# Power_iCESDuck-ShieldControler.net
KiCad netlist of a schematic drawn in EasyEDA
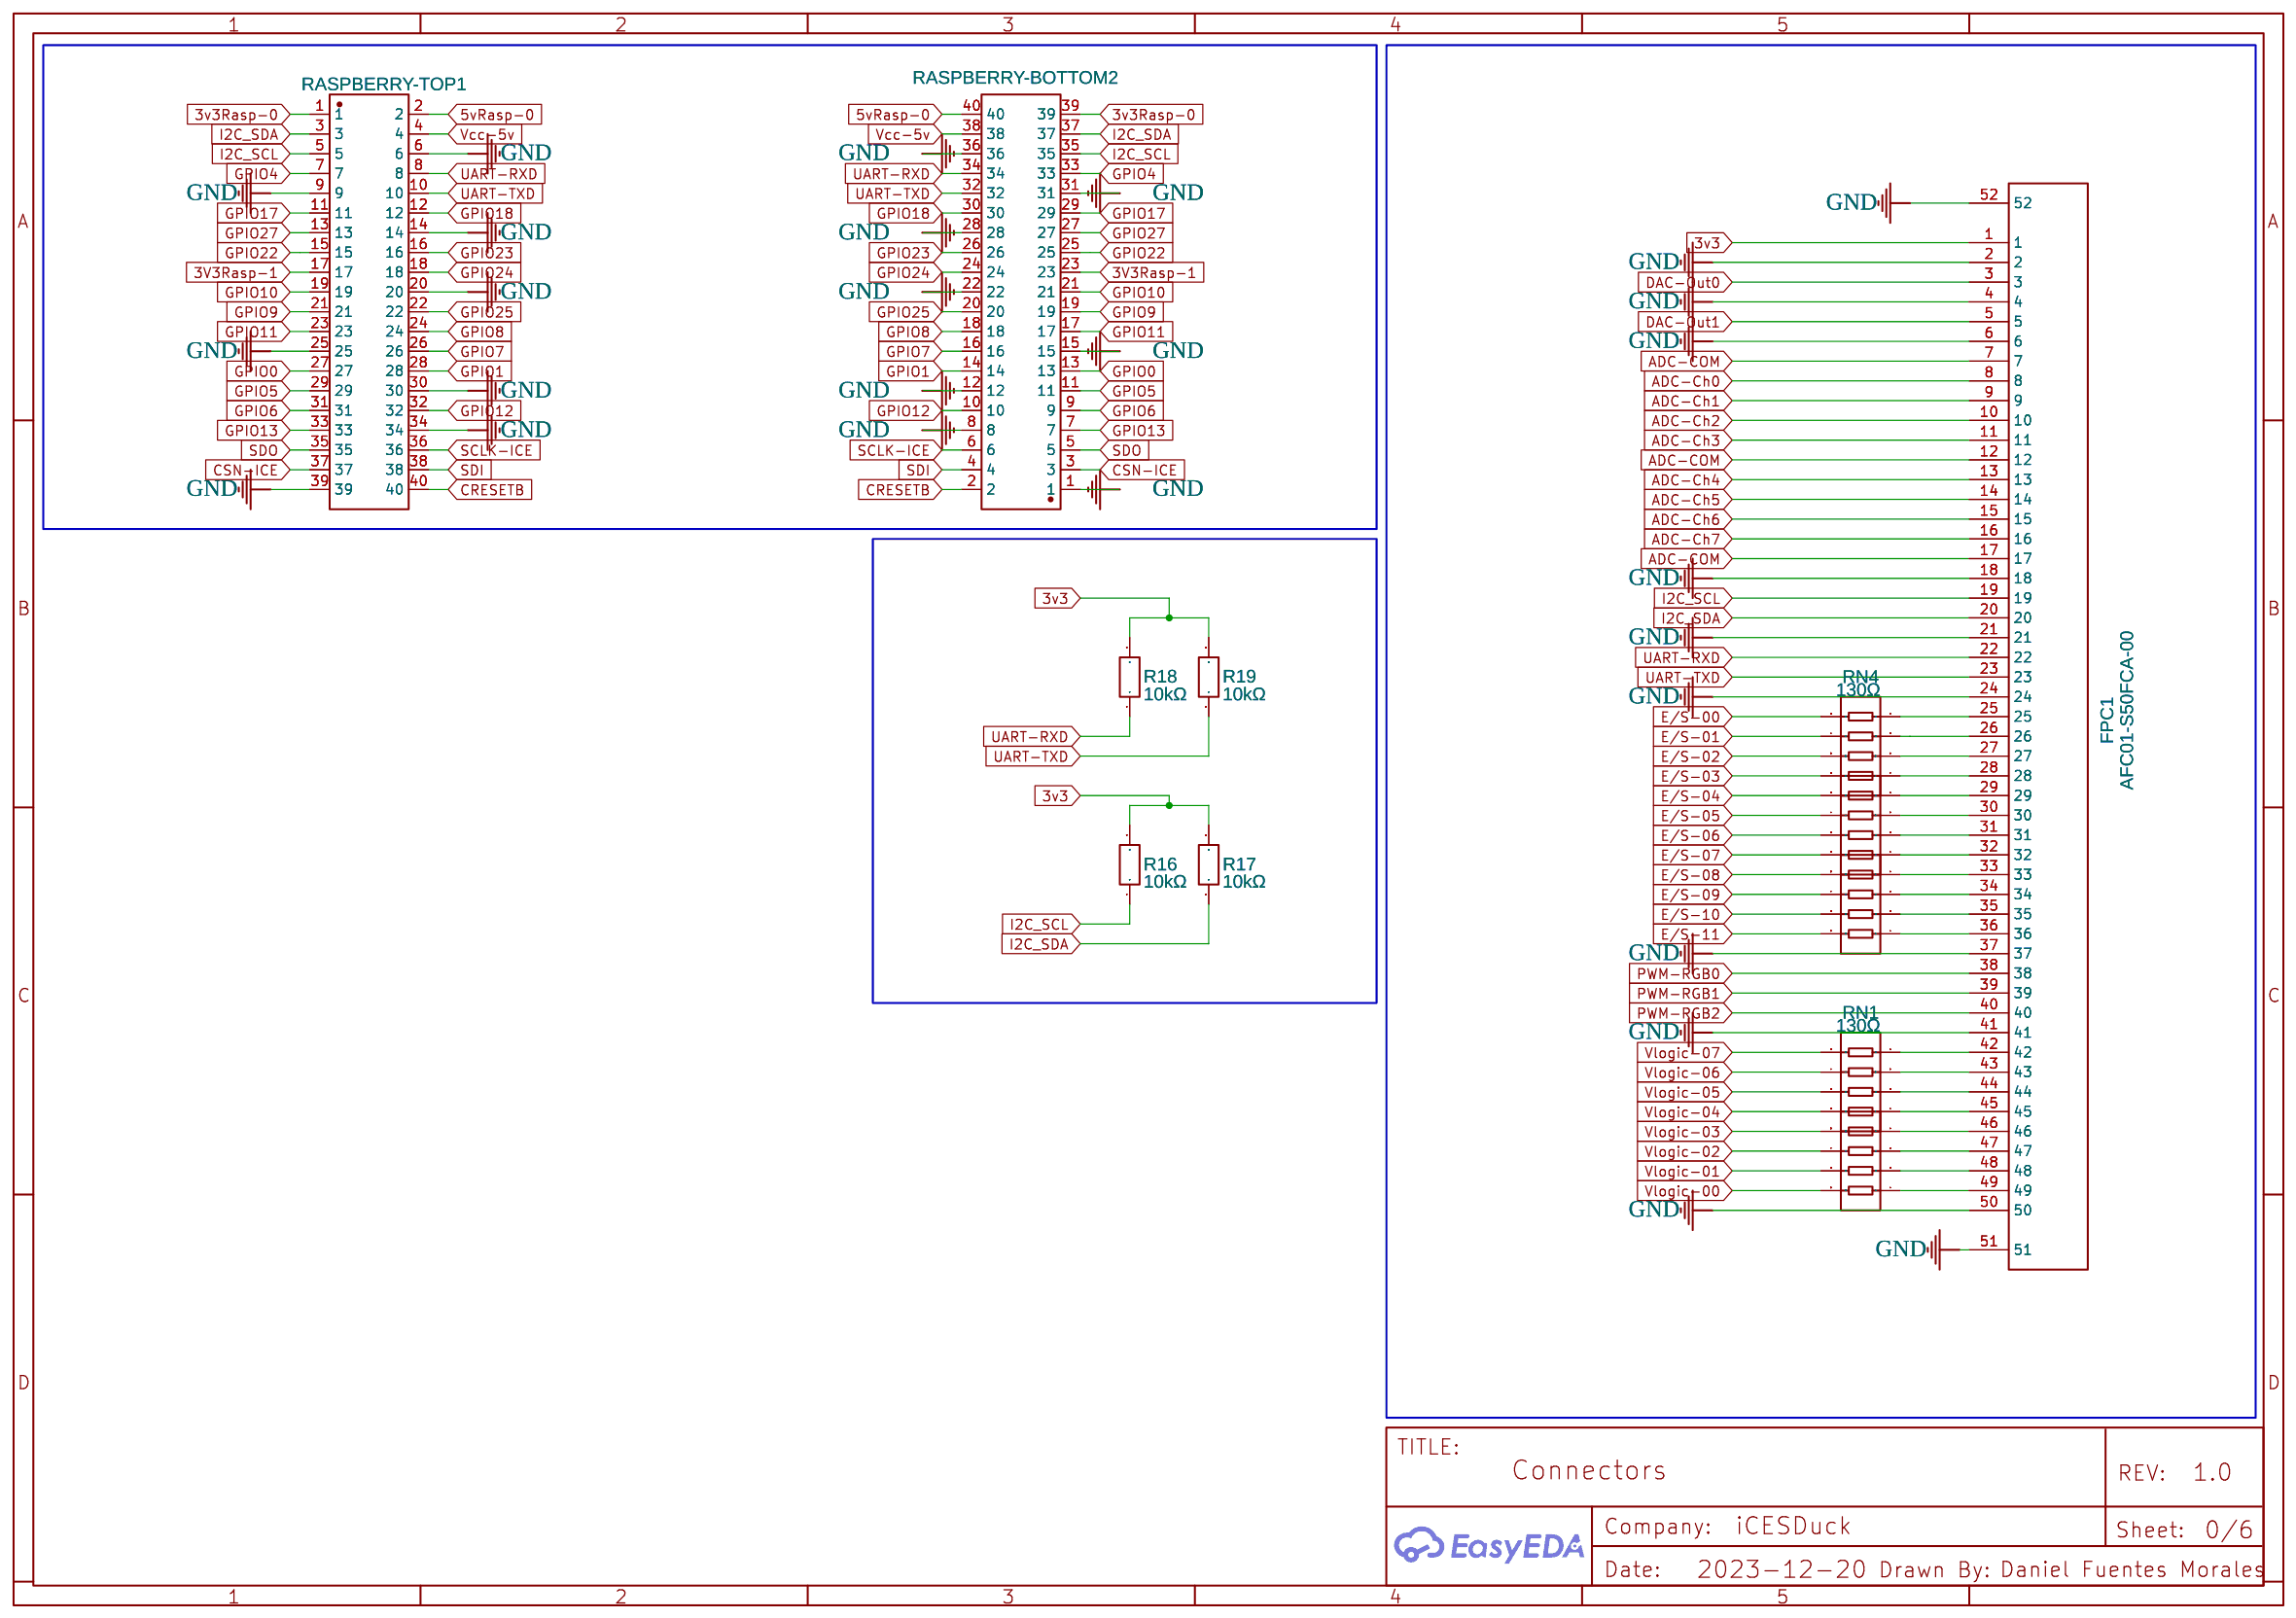
[diagram p0: Connectors]
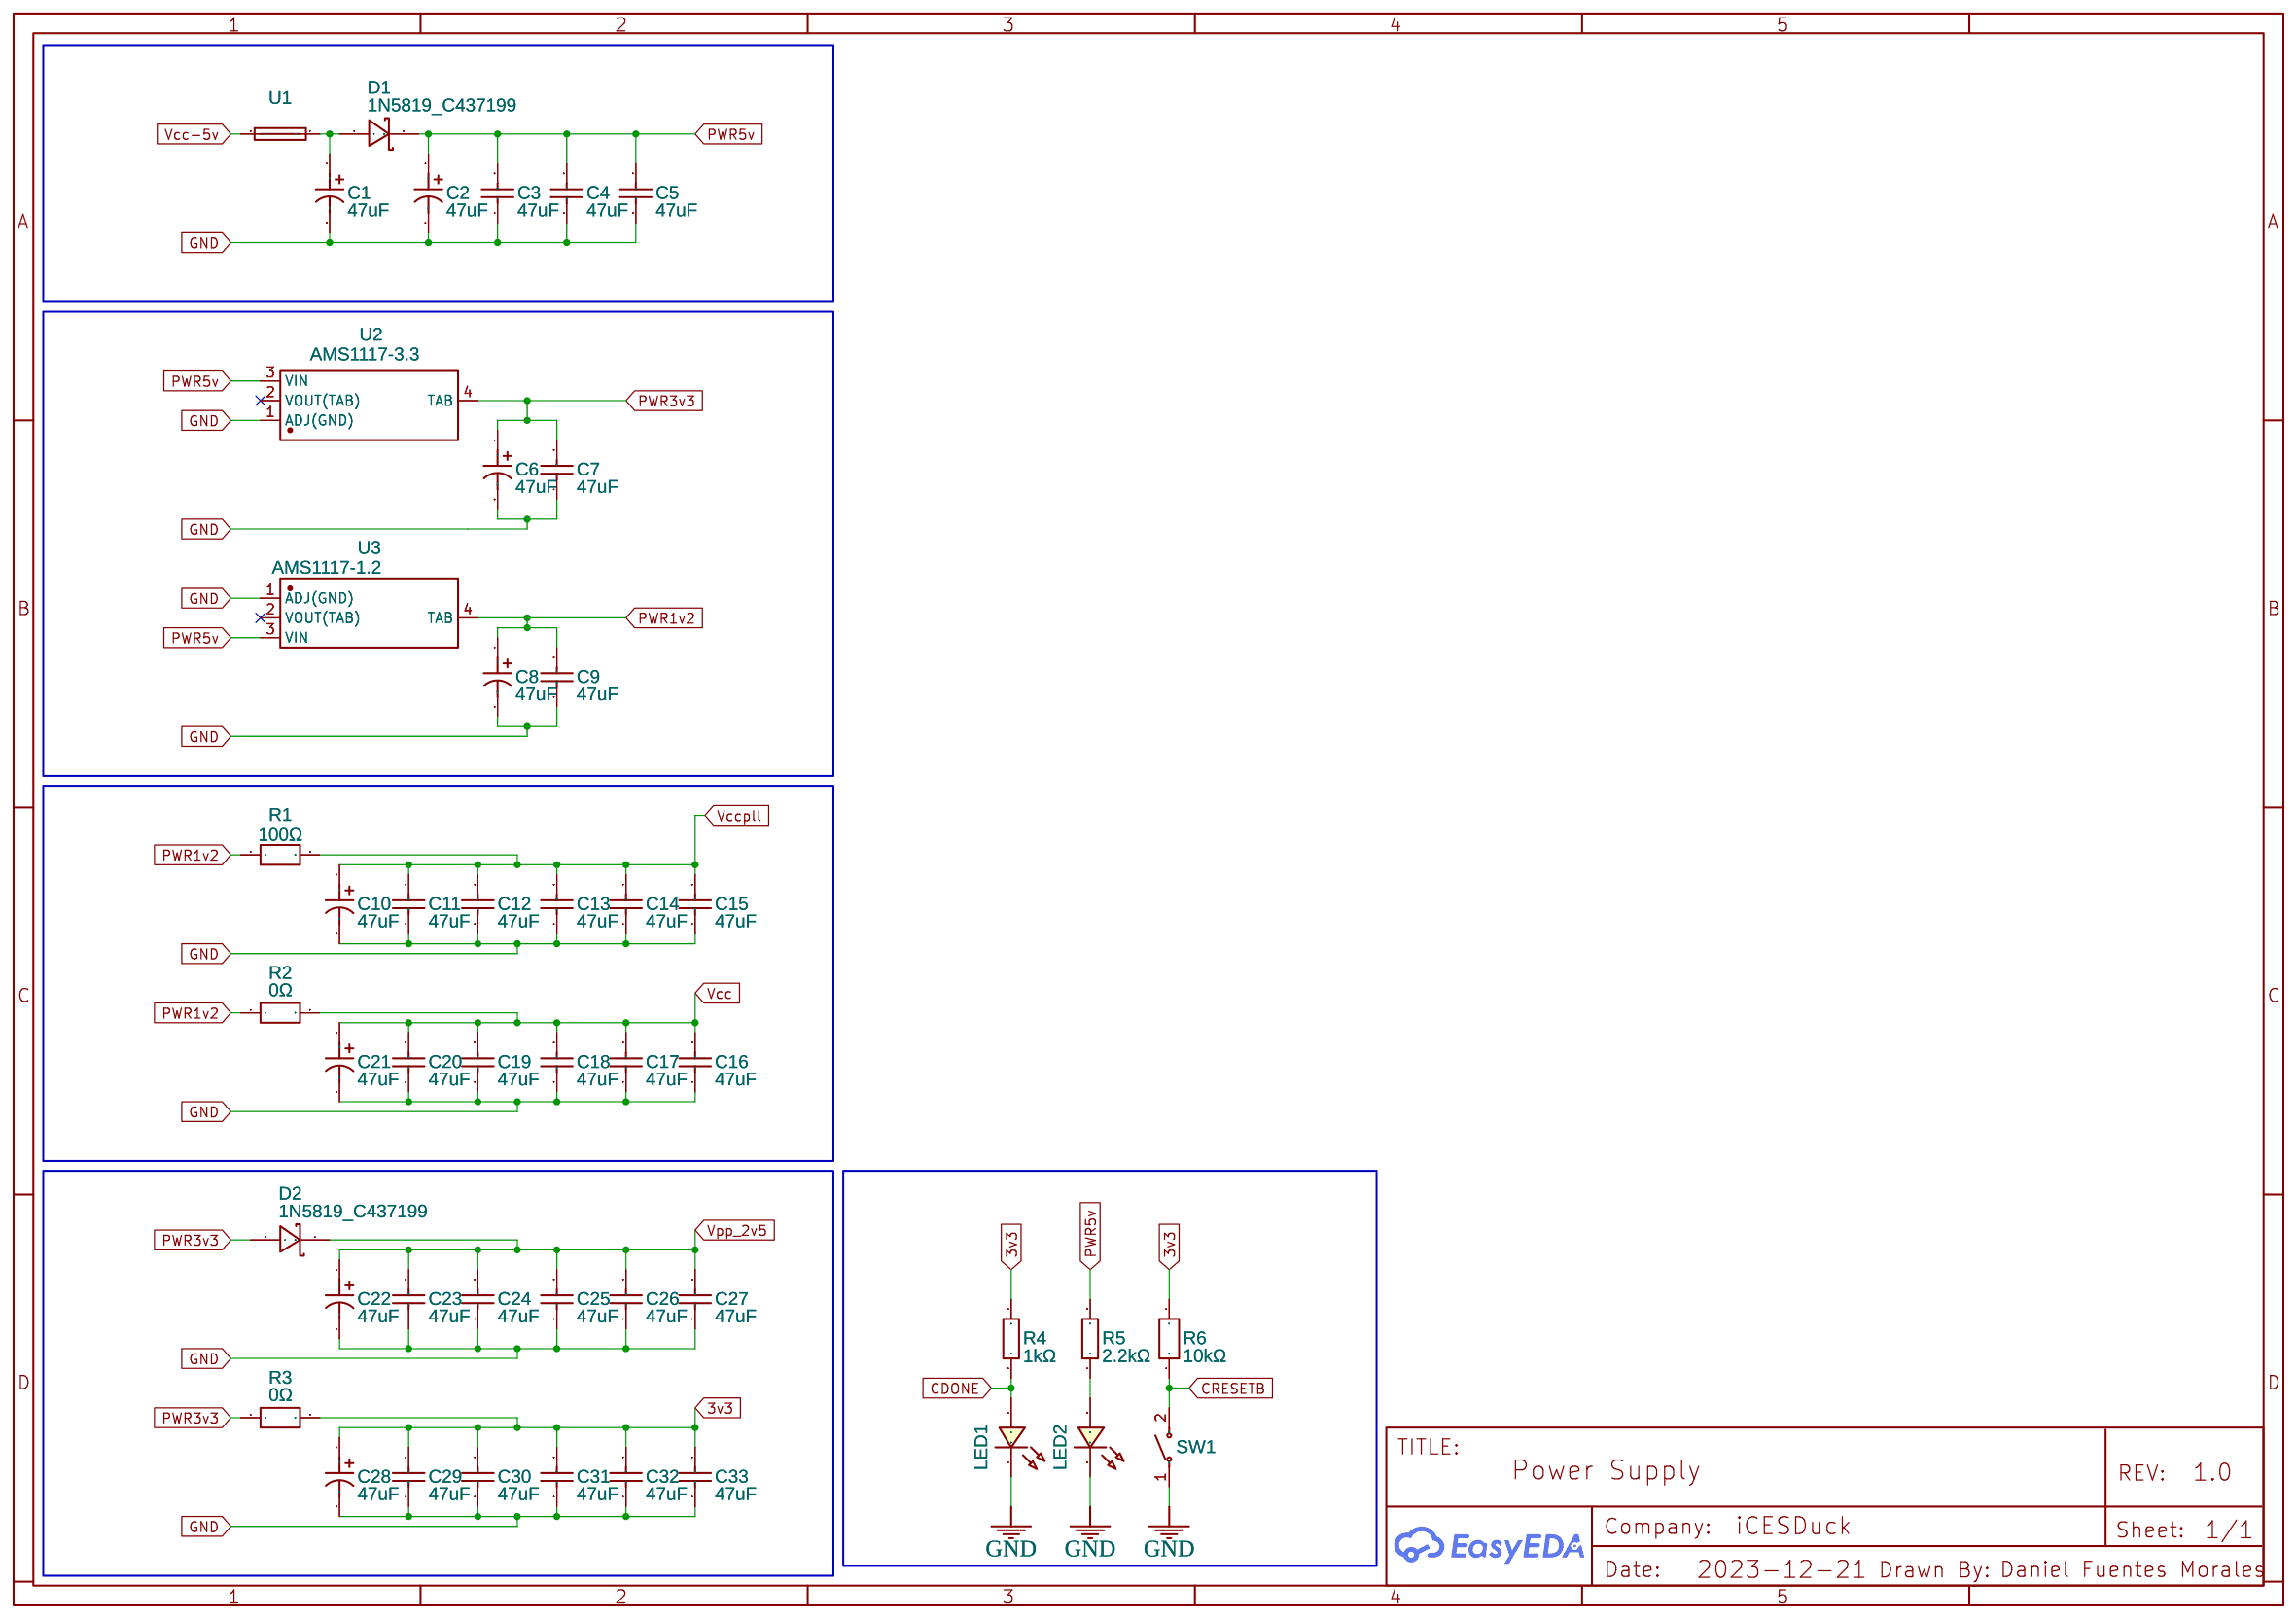
[diagram p1: power supply]
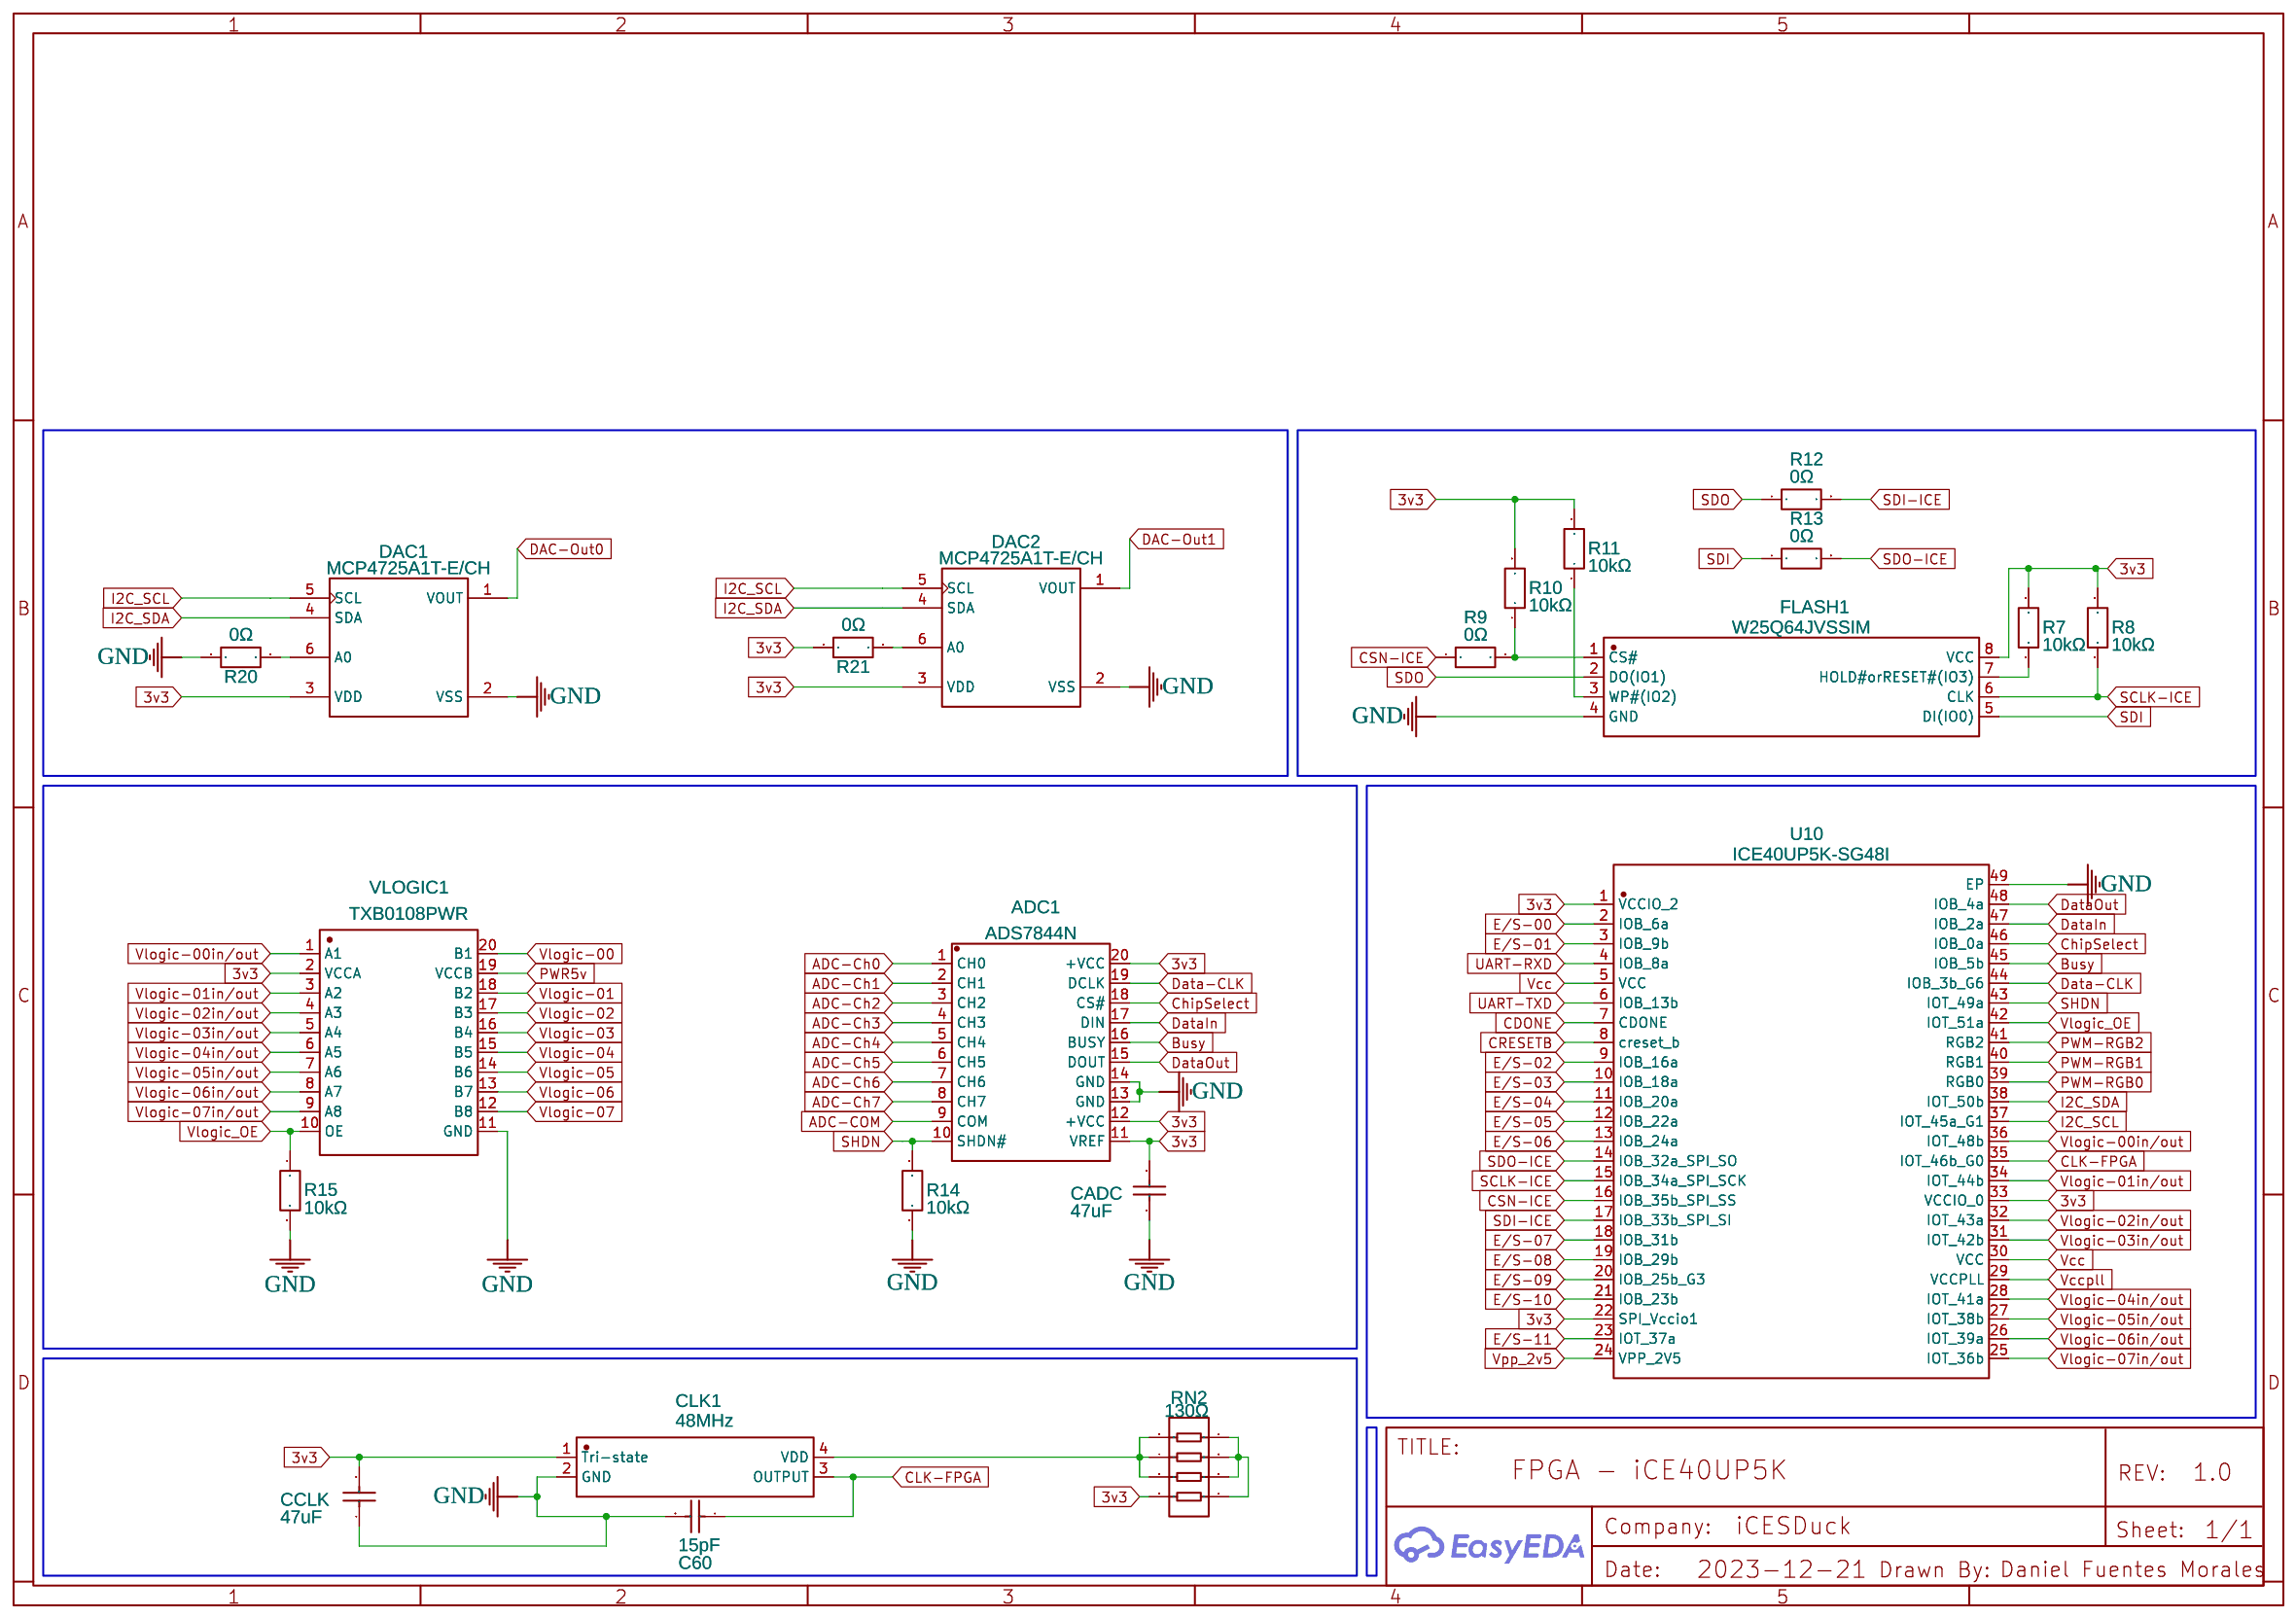
[diagram p2: FPGA - iCE40UP5k]

(export (version "E")
  (design (tool "Eeschema 10.0.6"))
  (components
    (comp (ref "FPC1")
      (value "AFC01-S50FCA-00")
      (fields (field (name "Manufacturer") "JS(钜硕电子)"))
      (libsource (lib "") (part "AFC01-S50FCA-00"))
    )
    (comp (ref "R16")
      (value "10kΩ")
      (fields (field (name "Manufacturer Part") "FRP1206J103 TS") (field (name "Manufacturer") "FOJAN(富捷)"))
      (libsource (lib "") (part "FRP1206J103 TS"))
    )
    (comp (ref "R17")
      (value "10kΩ")
      (fields (field (name "Manufacturer Part") "FRP1206J103 TS") (field (name "Manufacturer") "FOJAN(富捷)"))
      (libsource (lib "") (part "FRP1206J103 TS"))
    )
    (comp (ref "R18")
      (value "10kΩ")
      (fields (field (name "Manufacturer Part") "FRP1206J103 TS") (field (name "Manufacturer") "FOJAN(富捷)"))
      (libsource (lib "") (part "FRP1206J103 TS"))
    )
    (comp (ref "R19")
      (value "10kΩ")
      (fields (field (name "Manufacturer Part") "FRP1206J103 TS") (field (name "Manufacturer") "FOJAN(富捷)"))
      (libsource (lib "") (part "FRP1206J103 TS"))
    )
    (comp (ref "RASPBERRY-BOTTOM2")
      (value "FH-00148")
      (fields (field (name "Manufacturer") "Liansheng(连盛)"))
      (libsource (lib "") (part "FH-00148_1"))
    )
    (comp (ref "RASPBERRY-TOP1")
      (value "FH-00148")
      (fields (field (name "Manufacturer") "Liansheng(连盛)"))
      (libsource (lib "") (part "FH-00148"))
    )
    (comp (ref "RN1")
      (value "130Ω")
      (fields
        (field (name "Manufacturer Part") "4D03WGJ0131T5E")
        (field (name "Manufacturer") "UNI-ROYAL(厚声)")
      )
      (libsource (lib "") (part "4D03WGJ0131T5E"))
    )
    (comp (ref "RN3")
      (value "130Ω")
      (fields
        (field (name "Manufacturer Part") "4D03WGJ0131T5E")
        (field (name "Manufacturer") "UNI-ROYAL(厚声)")
      )
      (libsource (lib "") (part "4D03WGJ0131T5E"))
    )
    (comp (ref "RN4")
      (value "130Ω")
      (fields
        (field (name "Manufacturer Part") "4D03WGJ0131T5E")
        (field (name "Manufacturer") "UNI-ROYAL(厚声)")
      )
      (libsource (lib "") (part "4D03WGJ0131T5E"))
    )
    (comp (ref "RN5")
      (value "130Ω")
      (fields
        (field (name "Manufacturer Part") "4D03WGJ0131T5E")
        (field (name "Manufacturer") "UNI-ROYAL(厚声)")
      )
      (libsource (lib "") (part "4D03WGJ0131T5E"))
    )
    (comp (ref "RN6")
      (value "130Ω")
      (fields
        (field (name "Manufacturer Part") "4D03WGJ0131T5E")
        (field (name "Manufacturer") "UNI-ROYAL(厚声)")
      )
      (libsource (lib "") (part "4D03WGJ0131T5E"))
    )
    (comp (ref "C1")
      (value "47uF")
      (fields
        (field (name "Manufacturer Part") "CA45-A-10V-47uF-M")
        (field (name "Manufacturer") "CEC(振华新云)")
      )
      (libsource (lib "") (part "CA45-A-10V-47UF-M"))
    )
    (comp (ref "C2")
      (value "47uF")
      (fields
        (field (name "Manufacturer Part") "CA45-A-10V-47uF-M")
        (field (name "Manufacturer") "CEC(振华新云)")
      )
      (libsource (lib "") (part "CA45-A-10V-47UF-M"))
    )
    (comp (ref "C3")
      (value "47uF")
      (fields (field (name "Manufacturer Part") "C2012X5R1A476MTJ00E") (field (name "Manufacturer") "TDK"))
      (libsource (lib "") (part "C2012X5R1A476MTJ00E"))
    )
    (comp (ref "C4")
      (value "47uF")
      (fields (field (name "Manufacturer Part") "C2012X5R1A476MTJ00E") (field (name "Manufacturer") "TDK"))
      (libsource (lib "") (part "C2012X5R1A476MTJ00E"))
    )
    (comp (ref "C5")
      (value "47uF")
      (fields (field (name "Manufacturer Part") "C2012X5R1A476MTJ00E") (field (name "Manufacturer") "TDK"))
      (libsource (lib "") (part "C2012X5R1A476MTJ00E"))
    )
    (comp (ref "C6")
      (value "47uF")
      (fields
        (field (name "Manufacturer Part") "CA45-A-10V-47uF-M")
        (field (name "Manufacturer") "CEC(振华新云)")
      )
      (libsource (lib "") (part "CA45-A-10V-47UF-M"))
    )
    (comp (ref "C7")
      (value "47uF")
      (fields (field (name "Manufacturer Part") "C2012X5R1A476MTJ00E") (field (name "Manufacturer") "TDK"))
      (libsource (lib "") (part "C2012X5R1A476MTJ00E"))
    )
    (comp (ref "C8")
      (value "47uF")
      (fields
        (field (name "Manufacturer Part") "CA45-A-10V-47uF-M")
        (field (name "Manufacturer") "CEC(振华新云)")
      )
      (libsource (lib "") (part "CA45-A-10V-47UF-M"))
    )
    (comp (ref "C9")
      (value "47uF")
      (fields (field (name "Manufacturer Part") "C2012X5R1A476MTJ00E") (field (name "Manufacturer") "TDK"))
      (libsource (lib "") (part "C2012X5R1A476MTJ00E"))
    )
    (comp (ref "C10")
      (value "47uF")
      (fields
        (field (name "Manufacturer Part") "CA45-A-10V-47uF-M")
        (field (name "Manufacturer") "CEC(振华新云)")
      )
      (libsource (lib "") (part "CA45-A-10V-47UF-M"))
    )
    (comp (ref "C11")
      (value "47uF")
      (fields (field (name "Manufacturer Part") "C2012X5R1A476MTJ00E") (field (name "Manufacturer") "TDK"))
      (libsource (lib "") (part "C2012X5R1A476MTJ00E"))
    )
    (comp (ref "C12")
      (value "47uF")
      (fields (field (name "Manufacturer Part") "C2012X5R1A476MTJ00E") (field (name "Manufacturer") "TDK"))
      (libsource (lib "") (part "C2012X5R1A476MTJ00E"))
    )
    (comp (ref "C13")
      (value "47uF")
      (fields (field (name "Manufacturer Part") "C2012X5R1A476MTJ00E") (field (name "Manufacturer") "TDK"))
      (libsource (lib "") (part "C2012X5R1A476MTJ00E"))
    )
    (comp (ref "C14")
      (value "47uF")
      (fields (field (name "Manufacturer Part") "C2012X5R1A476MTJ00E") (field (name "Manufacturer") "TDK"))
      (libsource (lib "") (part "C2012X5R1A476MTJ00E"))
    )
    (comp (ref "C15")
      (value "47uF")
      (fields (field (name "Manufacturer Part") "C2012X5R1A476MTJ00E") (field (name "Manufacturer") "TDK"))
      (libsource (lib "") (part "C2012X5R1A476MTJ00E"))
    )
    (comp (ref "C16")
      (value "47uF")
      (fields (field (name "Manufacturer Part") "C2012X5R1A476MTJ00E") (field (name "Manufacturer") "TDK"))
      (libsource (lib "") (part "C2012X5R1A476MTJ00E"))
    )
    (comp (ref "C17")
      (value "47uF")
      (fields (field (name "Manufacturer Part") "C2012X5R1A476MTJ00E") (field (name "Manufacturer") "TDK"))
      (libsource (lib "") (part "C2012X5R1A476MTJ00E"))
    )
    (comp (ref "C18")
      (value "47uF")
      (fields (field (name "Manufacturer Part") "C2012X5R1A476MTJ00E") (field (name "Manufacturer") "TDK"))
      (libsource (lib "") (part "C2012X5R1A476MTJ00E"))
    )
    (comp (ref "C19")
      (value "47uF")
      (fields (field (name "Manufacturer Part") "C2012X5R1A476MTJ00E") (field (name "Manufacturer") "TDK"))
      (libsource (lib "") (part "C2012X5R1A476MTJ00E"))
    )
    (comp (ref "C20")
      (value "47uF")
      (fields (field (name "Manufacturer Part") "C2012X5R1A476MTJ00E") (field (name "Manufacturer") "TDK"))
      (libsource (lib "") (part "C2012X5R1A476MTJ00E"))
    )
    (comp (ref "C21")
      (value "47uF")
      (fields
        (field (name "Manufacturer Part") "CA45-A-10V-47uF-M")
        (field (name "Manufacturer") "CEC(振华新云)")
      )
      (libsource (lib "") (part "CA45-A-10V-47UF-M"))
    )
    (comp (ref "C22")
      (value "47uF")
      (fields
        (field (name "Manufacturer Part") "CA45-A-10V-47uF-M")
        (field (name "Manufacturer") "CEC(振华新云)")
      )
      (libsource (lib "") (part "CA45-A-10V-47UF-M"))
    )
    (comp (ref "C23")
      (value "47uF")
      (fields (field (name "Manufacturer Part") "C2012X5R1A476MTJ00E") (field (name "Manufacturer") "TDK"))
      (libsource (lib "") (part "C2012X5R1A476MTJ00E"))
    )
    (comp (ref "C24")
      (value "47uF")
      (fields (field (name "Manufacturer Part") "C2012X5R1A476MTJ00E") (field (name "Manufacturer") "TDK"))
      (libsource (lib "") (part "C2012X5R1A476MTJ00E"))
    )
    (comp (ref "C25")
      (value "47uF")
      (fields (field (name "Manufacturer Part") "C2012X5R1A476MTJ00E") (field (name "Manufacturer") "TDK"))
      (libsource (lib "") (part "C2012X5R1A476MTJ00E"))
    )
    (comp (ref "C26")
      (value "47uF")
      (fields (field (name "Manufacturer Part") "C2012X5R1A476MTJ00E") (field (name "Manufacturer") "TDK"))
      (libsource (lib "") (part "C2012X5R1A476MTJ00E"))
    )
    (comp (ref "C27")
      (value "47uF")
      (fields (field (name "Manufacturer Part") "C2012X5R1A476MTJ00E") (field (name "Manufacturer") "TDK"))
      (libsource (lib "") (part "C2012X5R1A476MTJ00E"))
    )
    (comp (ref "C28")
      (value "47uF")
      (fields
        (field (name "Manufacturer Part") "CA45-A-10V-47uF-M")
        (field (name "Manufacturer") "CEC(振华新云)")
      )
      (libsource (lib "") (part "CA45-A-10V-47UF-M"))
    )
    (comp (ref "C29")
      (value "47uF")
      (fields (field (name "Manufacturer Part") "C2012X5R1A476MTJ00E") (field (name "Manufacturer") "TDK"))
      (libsource (lib "") (part "C2012X5R1A476MTJ00E"))
    )
    (comp (ref "C30")
      (value "47uF")
      (fields (field (name "Manufacturer Part") "C2012X5R1A476MTJ00E") (field (name "Manufacturer") "TDK"))
      (libsource (lib "") (part "C2012X5R1A476MTJ00E"))
    )
    (comp (ref "C31")
      (value "47uF")
      (fields (field (name "Manufacturer Part") "C2012X5R1A476MTJ00E") (field (name "Manufacturer") "TDK"))
      (libsource (lib "") (part "C2012X5R1A476MTJ00E"))
    )
    (comp (ref "C32")
      (value "47uF")
      (fields (field (name "Manufacturer Part") "C2012X5R1A476MTJ00E") (field (name "Manufacturer") "TDK"))
      (libsource (lib "") (part "C2012X5R1A476MTJ00E"))
    )
    (comp (ref "C33")
      (value "47uF")
      (fields (field (name "Manufacturer Part") "C2012X5R1A476MTJ00E") (field (name "Manufacturer") "TDK"))
      (libsource (lib "") (part "C2012X5R1A476MTJ00E"))
    )
    (comp (ref "D1")
      (value "1N5819_C437199")
      (fields (field (name "Manufacturer Part") "1N5819") (field (name "Manufacturer") "KEXIN(科信)"))
      (libsource (lib "") (part "1N5819_C437199"))
    )
    (comp (ref "D2")
      (value "1N5819_C437199")
      (fields (field (name "Manufacturer Part") "1N5819") (field (name "Manufacturer") "KEXIN(科信)"))
      (libsource (lib "") (part "1N5819_C437199"))
    )
    (comp (ref "LED1")
      (value "LED-0603_G")
      (fields
        (field (name "Manufacturer Part") "19-217/GHC-YR1S2/3T")
        (field (name "Manufacturer") "EVERLIGHT(台湾亿光)")
      )
      (libsource (lib "") (part "LED-0603_G"))
    )
    (comp (ref "LED2")
      (value "LED-0603_G")
      (fields
        (field (name "Manufacturer Part") "19-217/GHC-YR1S2/3T")
        (field (name "Manufacturer") "EVERLIGHT(台湾亿光)")
      )
      (libsource (lib "") (part "LED-0603_G"))
    )
    (comp (ref "R1")
      (value "100Ω")
      (fields
        (field (name "Manufacturer Part") "AS05W2J0102T5E")
        (field (name "Manufacturer") "UNI-ROYAL(厚声)")
      )
      (libsource (lib "") (part "AS05W2J0102T5E"))
    )
    (comp (ref "R2")
      (value "0Ω")
      (fields
        (field (name "Manufacturer Part") "AS05W2J0102T5E")
        (field (name "Manufacturer") "UNI-ROYAL(厚声)")
      )
      (libsource (lib "") (part "AS05W2J0102T5E"))
    )
    (comp (ref "R3")
      (value "0Ω")
      (fields
        (field (name "Manufacturer Part") "AS05W2J0102T5E")
        (field (name "Manufacturer") "UNI-ROYAL(厚声)")
      )
      (libsource (lib "") (part "AS05W2J0102T5E"))
    )
    (comp (ref "R4")
      (value "1kΩ")
      (fields
        (field (name "Manufacturer Part") "0603WAF1001T5E")
        (field (name "Manufacturer") "UNI-ROYAL(厚声)")
      )
      (libsource (lib "") (part "0603WAF1001T5E"))
    )
    (comp (ref "R5")
      (value "2.2kΩ")
      (fields
        (field (name "Manufacturer Part") "0603WAF2201T5E")
        (field (name "Manufacturer") "UNI-ROYAL(厚声)")
      )
      (libsource (lib "") (part "0603WAF2201T5E"))
    )
    (comp (ref "R6")
      (value "10kΩ")
      (fields (field (name "Manufacturer Part") "FRP1206J103 TS") (field (name "Manufacturer") "FOJAN(富捷)"))
      (libsource (lib "") (part "FRP1206J103 TS"))
    )
    (comp (ref "SW1")
      (value "TS-1088R-02026")
      (fields (field (name "Manufacturer") "XUNPU(讯普)"))
      (libsource (lib "") (part "TS-1088R-02026"))
    )
    (comp (ref "U1")
      (value "0494001.NR")
      (fields (field (name "Manufacturer") "Littelfuse(美国力特)"))
      (libsource (lib "") (part "0494001.NR"))
    )
    (comp (ref "U2")
      (value "AMS1117-3.3")
      (fields (field (name "Manufacturer") "UMW(广东友台半导体)"))
      (libsource (lib "") (part "AMS1117-3.3_C347222"))
    )
    (comp (ref "U3")
      (value "AMS1117-1.2")
      (fields (field (name "Manufacturer") "UMW(广东友台半导体)"))
      (libsource (lib "") (part "AMS1117-1.2_C347218"))
    )
    (comp (ref "ADC1")
      (value "ADS7844N")
      (fields (field (name "Manufacturer") "TI(德州仪器)"))
      (libsource (lib "") (part "ADS7844N"))
    )
    (comp (ref "C60")
      (value "15pF")
      (fields
        (field (name "Manufacturer Part") "CL10C150JB8NNNC")
        (field (name "Manufacturer") "SAMSUNG(三星)")
      )
      (libsource (lib "") (part "CL10C150JB8NNNC"))
    )
    (comp (ref "CADC")
      (value "47uF")
      (fields (field (name "Manufacturer Part") "C2012X5R1A476MTJ00E") (field (name "Manufacturer") "TDK"))
      (libsource (lib "") (part "C2012X5R1A476MTJ00E_1"))
    )
    (comp (ref "CCLK")
      (value "47uF")
      (fields (field (name "Manufacturer Part") "C2012X5R1A476MTJ00E") (field (name "Manufacturer") "TDK"))
      (libsource (lib "") (part "C2012X5R1A476MTJ00E"))
    )
    (comp (ref "CLK1")
      (value "48MHz")
      (fields
        (field (name "Manufacturer Part") "S3D48.000000B20F30T")
        (field (name "Manufacturer") "SCTF(星通时频)")
      )
      (libsource (lib "") (part "S3D48.000000B20F30T"))
    )
    (comp (ref "DAC1")
      (value "MCP4725A1T-E/CH")
      (fields (field (name "Manufacturer") "MICROCHIP(美国微芯)"))
      (libsource (lib "") (part "MCP4725A1T-E/CH"))
    )
    (comp (ref "DAC2")
      (value "MCP4725A1T-E/CH")
      (fields (field (name "Manufacturer") "MICROCHIP(美国微芯)"))
      (libsource (lib "") (part "MCP4725A1T-E/CH"))
    )
    (comp (ref "FLASH1")
      (value "W25Q64JVSSIM")
      (fields (field (name "Manufacturer") "WINBOND(华邦)"))
      (libsource (lib "") (part "W25Q64JVSSIM"))
    )
    (comp (ref "R7")
      (value "10kΩ")
      (fields (field (name "Manufacturer Part") "FRP1206J103 TS") (field (name "Manufacturer") "FOJAN(富捷)"))
      (libsource (lib "") (part "FRP1206J103 TS"))
    )
    (comp (ref "R8")
      (value "10kΩ")
      (fields (field (name "Manufacturer Part") "FRP1206J103 TS") (field (name "Manufacturer") "FOJAN(富捷)"))
      (libsource (lib "") (part "FRP1206J103 TS"))
    )
    (comp (ref "R9")
      (value "0Ω")
      (fields
        (field (name "Manufacturer Part") "AS05W2J0102T5E")
        (field (name "Manufacturer") "UNI-ROYAL(厚声)")
      )
      (libsource (lib "") (part "AS05W2J0102T5E"))
    )
    (comp (ref "R10")
      (value "10kΩ")
      (fields (field (name "Manufacturer Part") "FRP1206J103 TS") (field (name "Manufacturer") "FOJAN(富捷)"))
      (libsource (lib "") (part "FRP1206J103 TS"))
    )
    (comp (ref "R11")
      (value "10kΩ")
      (fields (field (name "Manufacturer Part") "FRP1206J103 TS") (field (name "Manufacturer") "FOJAN(富捷)"))
      (libsource (lib "") (part "FRP1206J103 TS"))
    )
    (comp (ref "R12")
      (value "0Ω")
      (fields
        (field (name "Manufacturer Part") "AS05W2J0102T5E")
        (field (name "Manufacturer") "UNI-ROYAL(厚声)")
      )
      (libsource (lib "") (part "AS05W2J0102T5E"))
    )
    (comp (ref "R13")
      (value "0Ω")
      (fields
        (field (name "Manufacturer Part") "AS05W2J0102T5E")
        (field (name "Manufacturer") "UNI-ROYAL(厚声)")
      )
      (libsource (lib "") (part "AS05W2J0102T5E"))
    )
    (comp (ref "R14")
      (value "10kΩ")
      (fields (field (name "Manufacturer Part") "FRP1206J103 TS") (field (name "Manufacturer") "FOJAN(富捷)"))
      (libsource (lib "") (part "FRP1206J103 TS"))
    )
    (comp (ref "R15")
      (value "10kΩ")
      (fields (field (name "Manufacturer Part") "FRP1206J103 TS") (field (name "Manufacturer") "FOJAN(富捷)"))
      (libsource (lib "") (part "FRP1206J103 TS_1"))
    )
    (comp (ref "R20")
      (value "0Ω")
      (fields
        (field (name "Manufacturer Part") "AS05W2J0102T5E")
        (field (name "Manufacturer") "UNI-ROYAL(厚声)")
      )
      (libsource (lib "") (part "AS05W2J0102T5E"))
    )
    (comp (ref "R21")
      (value "0Ω")
      (fields
        (field (name "Manufacturer Part") "AS05W2J0102T5E")
        (field (name "Manufacturer") "UNI-ROYAL(厚声)")
      )
      (libsource (lib "") (part "AS05W2J0102T5E"))
    )
    (comp (ref "RN2")
      (value "130Ω")
      (fields
        (field (name "Manufacturer Part") "4D03WGJ0131T5E")
        (field (name "Manufacturer") "UNI-ROYAL(厚声)")
      )
      (libsource (lib "") (part "4D03WGJ0131T5E"))
    )
    (comp (ref "U10")
      (value "ICE40UP5K-SG48I")
      (fields (field (name "Manufacturer") "LATTICE(莱迪思)"))
      (libsource (lib "") (part "ICE40UP5K-SG48I"))
    )
    (comp (ref "VLOGIC1")
      (value "TXB0108PWR")
      (fields (field (name "Manufacturer") "TI(德州仪器)"))
      (libsource (lib "") (part "TXB0108PWR"))
    )
  )
  (nets
    (net (code "1") (name "3V3Rasp-1") (class "Default")
      (node (ref "RASPBERRY-BOTTOM2") (pin "23") (pinfunction "23_23") (pintype "unspecified"))
      (node (ref "RASPBERRY-TOP1") (pin "17") (pinfunction "17_17") (pintype "unspecified"))
    )
    (net (code "2") (name "3v3") (class "Default")
      (node (ref "ADC1") (pin "11") (pinfunction "VREF_11") (pintype "unspecified"))
      (node (ref "ADC1") (pin "12") (pinfunction "+VCC_12") (pintype "unspecified"))
      (node (ref "ADC1") (pin "20") (pinfunction "+VCC_20") (pintype "unspecified"))
      (node (ref "C28") (pin "1") (pinfunction "1_1") (pintype "input"))
      (node (ref "C29") (pin "2") (pinfunction "2_2") (pintype "input"))
      (node (ref "C30") (pin "2") (pinfunction "2_2") (pintype "input"))
      (node (ref "C31") (pin "2") (pinfunction "2_2") (pintype "input"))
      (node (ref "C32") (pin "2") (pinfunction "2_2") (pintype "input"))
      (node (ref "C33") (pin "2") (pinfunction "2_2") (pintype "input"))
      (node (ref "CADC") (pin "2") (pinfunction "2_2") (pintype "input"))
      (node (ref "CCLK") (pin "2") (pinfunction "2_2") (pintype "input"))
      (node (ref "CLK1") (pin "1") (pinfunction "Tri-state_1") (pintype "unspecified"))
      (node (ref "DAC1") (pin "3") (pinfunction "VDD_3") (pintype "passive"))
      (node (ref "DAC2") (pin "3") (pinfunction "VDD_3") (pintype "passive"))
      (node (ref "FLASH1") (pin "8") (pinfunction "VCC_8") (pintype "unspecified"))
      (node (ref "FPC1") (pin "1") (pinfunction "1_1") (pintype "unspecified"))
      (node (ref "R10") (pin "2") (pinfunction "2_2") (pintype "unspecified"))
      (node (ref "R11") (pin "2") (pinfunction "2_2") (pintype "unspecified"))
      (node (ref "R16") (pin "2") (pinfunction "2_2") (pintype "unspecified"))
      (node (ref "R17") (pin "2") (pinfunction "2_2") (pintype "unspecified"))
      (node (ref "R18") (pin "2") (pinfunction "2_2") (pintype "unspecified"))
      (node (ref "R19") (pin "2") (pinfunction "2_2") (pintype "unspecified"))
      (node (ref "R21") (pin "1") (pinfunction "1_1") (pintype "unspecified"))
      (node (ref "R3") (pin "2") (pinfunction "2_2") (pintype "unspecified"))
      (node (ref "R4") (pin "2") (pinfunction "2_2") (pintype "input"))
      (node (ref "R6") (pin "2") (pinfunction "2_2") (pintype "unspecified"))
      (node (ref "R7") (pin "2") (pinfunction "2_2") (pintype "unspecified"))
      (node (ref "R8") (pin "2") (pinfunction "2_2") (pintype "unspecified"))
      (node (ref "RN2") (pin "5") (pinfunction "5_5") (pintype "unspecified"))
      (node (ref "U10") (pin "1") (pinfunction "VCCIO_2_1") (pintype "unspecified"))
      (node (ref "U10") (pin "22") (pinfunction "SPI_Vccio1_22") (pintype "unspecified"))
      (node (ref "U10") (pin "33") (pinfunction "VCCIO_0_33") (pintype "unspecified"))
      (node (ref "VLOGIC1") (pin "2") (pinfunction "VCCA_2") (pintype "unspecified"))
    )
    (net (code "3") (name "3v3Rasp-0") (class "Default")
      (node (ref "RASPBERRY-BOTTOM2") (pin "39") (pinfunction "39_39") (pintype "unspecified"))
      (node (ref "RASPBERRY-TOP1") (pin "1") (pinfunction "1_1") (pintype "unspecified"))
    )
    (net (code "4") (name "5vRasp-0") (class "Default")
      (node (ref "RASPBERRY-BOTTOM2") (pin "40") (pinfunction "40_40") (pintype "unspecified"))
      (node (ref "RASPBERRY-TOP1") (pin "2") (pinfunction "2_2") (pintype "unspecified"))
    )
    (net (code "5") (name "ADC-COM") (class "Default")
      (node (ref "ADC1") (pin "9") (pinfunction "COM_9") (pintype "unspecified"))
      (node (ref "FPC1") (pin "12") (pinfunction "12_12") (pintype "unspecified"))
      (node (ref "FPC1") (pin "17") (pinfunction "17_17") (pintype "unspecified"))
      (node (ref "FPC1") (pin "7") (pinfunction "7_7") (pintype "unspecified"))
    )
    (net (code "6") (name "ADC-Ch0") (class "Default")
      (node (ref "ADC1") (pin "1") (pinfunction "CH0_1") (pintype "unspecified"))
      (node (ref "FPC1") (pin "8") (pinfunction "8_8") (pintype "unspecified"))
    )
    (net (code "7") (name "ADC-Ch1") (class "Default")
      (node (ref "ADC1") (pin "2") (pinfunction "CH1_2") (pintype "unspecified"))
      (node (ref "FPC1") (pin "9") (pinfunction "9_9") (pintype "unspecified"))
    )
    (net (code "8") (name "ADC-Ch2") (class "Default")
      (node (ref "ADC1") (pin "3") (pinfunction "CH2_3") (pintype "unspecified"))
      (node (ref "FPC1") (pin "10") (pinfunction "10_10") (pintype "unspecified"))
    )
    (net (code "9") (name "ADC-Ch3") (class "Default")
      (node (ref "ADC1") (pin "4") (pinfunction "CH3_4") (pintype "unspecified"))
      (node (ref "FPC1") (pin "11") (pinfunction "11_11") (pintype "unspecified"))
    )
    (net (code "10") (name "ADC-Ch4") (class "Default")
      (node (ref "ADC1") (pin "5") (pinfunction "CH4_5") (pintype "unspecified"))
      (node (ref "FPC1") (pin "13") (pinfunction "13_13") (pintype "unspecified"))
    )
    (net (code "11") (name "ADC-Ch5") (class "Default")
      (node (ref "ADC1") (pin "6") (pinfunction "CH5_6") (pintype "unspecified"))
      (node (ref "FPC1") (pin "14") (pinfunction "14_14") (pintype "unspecified"))
    )
    (net (code "12") (name "ADC-Ch6") (class "Default")
      (node (ref "ADC1") (pin "7") (pinfunction "CH6_7") (pintype "unspecified"))
      (node (ref "FPC1") (pin "15") (pinfunction "15_15") (pintype "unspecified"))
    )
    (net (code "13") (name "ADC-Ch7") (class "Default")
      (node (ref "ADC1") (pin "8") (pinfunction "CH7_8") (pintype "unspecified"))
      (node (ref "FPC1") (pin "16") (pinfunction "16_16") (pintype "unspecified"))
    )
    (net (code "14") (name "Busy") (class "Default")
      (node (ref "ADC1") (pin "16") (pinfunction "BUSY_16") (pintype "unspecified"))
      (node (ref "U10") (pin "45") (pinfunction "IOB_5b_45") (pintype "unspecified"))
    )
    (net (code "15") (name "CDONE") (class "Default")
      (node (ref "LED1") (pin "1") (pinfunction "1_1") (pintype "unspecified"))
      (node (ref "R4") (pin "1") (pinfunction "1_1") (pintype "input"))
      (node (ref "U10") (pin "7") (pinfunction "CDONE_7") (pintype "unspecified"))
    )
    (net (code "16") (name "CLK-FPGA") (class "Default")
      (node (ref "C60") (pin "1") (pinfunction "1_1") (pintype "input"))
      (node (ref "CLK1") (pin "3") (pinfunction "OUTPUT_3") (pintype "unspecified"))
      (node (ref "U10") (pin "35") (pinfunction "IOT_46b_G0_35") (pintype "unspecified"))
    )
    (net (code "17") (name "CRESETB") (class "Default")
      (node (ref "R6") (pin "1") (pinfunction "1_1") (pintype "unspecified"))
      (node (ref "RASPBERRY-BOTTOM2") (pin "2") (pinfunction "2_2") (pintype "unspecified"))
      (node (ref "RASPBERRY-TOP1") (pin "40") (pinfunction "40_40") (pintype "unspecified"))
      (node (ref "SW1") (pin "2") (pinfunction "2_2") (pintype "unspecified"))
      (node (ref "U10") (pin "8") (pinfunction "creset_b_8") (pintype "unspecified"))
    )
    (net (code "18") (name "CSN-ICE") (class "Default")
      (node (ref "R9") (pin "1") (pinfunction "1_1") (pintype "unspecified"))
      (node (ref "RASPBERRY-BOTTOM2") (pin "3") (pinfunction "3_3") (pintype "unspecified"))
      (node (ref "RASPBERRY-TOP1") (pin "37") (pinfunction "37_37") (pintype "unspecified"))
      (node (ref "U10") (pin "16") (pinfunction "IOB_35b_SPI_SS_16") (pintype "unspecified"))
    )
    (net (code "19") (name "ChipSelect") (class "Default")
      (node (ref "ADC1") (pin "18") (pinfunction "CS#_18") (pintype "unspecified"))
      (node (ref "U10") (pin "46") (pinfunction "IOB_0a_46") (pintype "unspecified"))
    )
    (net (code "20") (name "DAC-Out0") (class "Default")
      (node (ref "DAC1") (pin "1") (pinfunction "VOUT_1") (pintype "output"))
      (node (ref "FPC1") (pin "3") (pinfunction "3_3") (pintype "unspecified"))
    )
    (net (code "21") (name "DAC-Out1") (class "Default")
      (node (ref "DAC2") (pin "1") (pinfunction "VOUT_1") (pintype "output"))
      (node (ref "FPC1") (pin "5") (pinfunction "5_5") (pintype "unspecified"))
    )
    (net (code "22") (name "Data-CLK") (class "Default")
      (node (ref "ADC1") (pin "19") (pinfunction "DCLK_19") (pintype "unspecified"))
      (node (ref "U10") (pin "44") (pinfunction "IOB_3b_G6_44") (pintype "unspecified"))
    )
    (net (code "23") (name "DataIn") (class "Default")
      (node (ref "ADC1") (pin "17") (pinfunction "DIN_17") (pintype "unspecified"))
      (node (ref "U10") (pin "47") (pinfunction "IOB_2a_47") (pintype "unspecified"))
    )
    (net (code "24") (name "DataOut") (class "Default")
      (node (ref "ADC1") (pin "15") (pinfunction "DOUT_15") (pintype "unspecified"))
      (node (ref "U10") (pin "48") (pinfunction "IOB_4a_48") (pintype "unspecified"))
    )
    (net (code "25") (name "E{slash}S-00") (class "Default")
      (node (ref "RN4") (pin "8") (pinfunction "8_8") (pintype "unspecified"))
      (node (ref "U10") (pin "2") (pinfunction "IOB_6a_2") (pintype "unspecified"))
    )
    (net (code "26") (name "E{slash}S-01") (class "Default")
      (node (ref "RN4") (pin "7") (pinfunction "7_7") (pintype "unspecified"))
      (node (ref "U10") (pin "3") (pinfunction "IOB_9b_3") (pintype "unspecified"))
    )
    (net (code "27") (name "E{slash}S-02") (class "Default")
      (node (ref "RN4") (pin "6") (pinfunction "6_6") (pintype "unspecified"))
      (node (ref "U10") (pin "9") (pinfunction "IOB_16a_9") (pintype "unspecified"))
    )
    (net (code "28") (name "E{slash}S-03") (class "Default")
      (node (ref "RN4") (pin "5") (pinfunction "5_5") (pintype "unspecified"))
      (node (ref "U10") (pin "10") (pinfunction "IOB_18a_10") (pintype "unspecified"))
    )
    (net (code "29") (name "E{slash}S-04") (class "Default")
      (node (ref "RN5") (pin "8") (pinfunction "8_8") (pintype "unspecified"))
      (node (ref "U10") (pin "11") (pinfunction "IOB_20a_11") (pintype "unspecified"))
    )
    (net (code "30") (name "E{slash}S-05") (class "Default")
      (node (ref "RN5") (pin "7") (pinfunction "7_7") (pintype "unspecified"))
      (node (ref "U10") (pin "12") (pinfunction "IOB_22a_12") (pintype "unspecified"))
    )
    (net (code "31") (name "E{slash}S-06") (class "Default")
      (node (ref "RN5") (pin "6") (pinfunction "6_6") (pintype "unspecified"))
      (node (ref "U10") (pin "13") (pinfunction "IOB_24a_13") (pintype "unspecified"))
    )
    (net (code "32") (name "E{slash}S-07") (class "Default")
      (node (ref "RN5") (pin "5") (pinfunction "5_5") (pintype "unspecified"))
      (node (ref "U10") (pin "18") (pinfunction "IOB_31b_18") (pintype "unspecified"))
    )
    (net (code "33") (name "E{slash}S-08") (class "Default")
      (node (ref "RN6") (pin "8") (pinfunction "8_8") (pintype "unspecified"))
      (node (ref "U10") (pin "19") (pinfunction "IOB_29b_19") (pintype "unspecified"))
    )
    (net (code "34") (name "E{slash}S-09") (class "Default")
      (node (ref "RN6") (pin "7") (pinfunction "7_7") (pintype "unspecified"))
      (node (ref "U10") (pin "20") (pinfunction "IOB_25b_G3_20") (pintype "unspecified"))
    )
    (net (code "35") (name "E{slash}S-10") (class "Default")
      (node (ref "RN6") (pin "6") (pinfunction "6_6") (pintype "unspecified"))
      (node (ref "U10") (pin "21") (pinfunction "IOB_23b_21") (pintype "unspecified"))
    )
    (net (code "36") (name "E{slash}S-11") (class "Default")
      (node (ref "RN6") (pin "5") (pinfunction "5_5") (pintype "unspecified"))
      (node (ref "U10") (pin "23") (pinfunction "IOT_37a_23") (pintype "unspecified"))
    )
    (net (code "37") (name "GND") (class "Default")
      (node (ref "ADC1") (pin "13") (pinfunction "GND_13") (pintype "unspecified"))
      (node (ref "ADC1") (pin "14") (pinfunction "GND_14") (pintype "unspecified"))
      (node (ref "C1") (pin "2") (pinfunction "2_2") (pintype "input"))
      (node (ref "C10") (pin "2") (pinfunction "2_2") (pintype "input"))
      (node (ref "C11") (pin "1") (pinfunction "1_1") (pintype "input"))
      (node (ref "C12") (pin "1") (pinfunction "1_1") (pintype "input"))
      (node (ref "C13") (pin "1") (pinfunction "1_1") (pintype "input"))
      (node (ref "C14") (pin "1") (pinfunction "1_1") (pintype "input"))
      (node (ref "C15") (pin "1") (pinfunction "1_1") (pintype "input"))
      (node (ref "C16") (pin "1") (pinfunction "1_1") (pintype "input"))
      (node (ref "C17") (pin "1") (pinfunction "1_1") (pintype "input"))
      (node (ref "C18") (pin "1") (pinfunction "1_1") (pintype "input"))
      (node (ref "C19") (pin "1") (pinfunction "1_1") (pintype "input"))
      (node (ref "C2") (pin "2") (pinfunction "2_2") (pintype "input"))
      (node (ref "C20") (pin "1") (pinfunction "1_1") (pintype "input"))
      (node (ref "C21") (pin "2") (pinfunction "2_2") (pintype "input"))
      (node (ref "C22") (pin "2") (pinfunction "2_2") (pintype "input"))
      (node (ref "C23") (pin "1") (pinfunction "1_1") (pintype "input"))
      (node (ref "C24") (pin "1") (pinfunction "1_1") (pintype "input"))
      (node (ref "C25") (pin "1") (pinfunction "1_1") (pintype "input"))
      (node (ref "C26") (pin "1") (pinfunction "1_1") (pintype "input"))
      (node (ref "C27") (pin "1") (pinfunction "1_1") (pintype "input"))
      (node (ref "C28") (pin "2") (pinfunction "2_2") (pintype "input"))
      (node (ref "C29") (pin "1") (pinfunction "1_1") (pintype "input"))
      (node (ref "C3") (pin "1") (pinfunction "1_1") (pintype "input"))
      (node (ref "C30") (pin "1") (pinfunction "1_1") (pintype "input"))
      (node (ref "C31") (pin "1") (pinfunction "1_1") (pintype "input"))
      (node (ref "C32") (pin "1") (pinfunction "1_1") (pintype "input"))
      (node (ref "C33") (pin "1") (pinfunction "1_1") (pintype "input"))
      (node (ref "C4") (pin "1") (pinfunction "1_1") (pintype "input"))
      (node (ref "C5") (pin "1") (pinfunction "1_1") (pintype "input"))
      (node (ref "C6") (pin "2") (pinfunction "2_2") (pintype "input"))
      (node (ref "C60") (pin "2") (pinfunction "2_2") (pintype "input"))
      (node (ref "C7") (pin "1") (pinfunction "1_1") (pintype "input"))
      (node (ref "C8") (pin "2") (pinfunction "2_2") (pintype "input"))
      (node (ref "C9") (pin "1") (pinfunction "1_1") (pintype "input"))
      (node (ref "CADC") (pin "1") (pinfunction "1_1") (pintype "input"))
      (node (ref "CCLK") (pin "1") (pinfunction "1_1") (pintype "input"))
      (node (ref "CLK1") (pin "2") (pinfunction "GND_2") (pintype "unspecified"))
      (node (ref "DAC1") (pin "2") (pinfunction "VSS_2") (pintype "passive"))
      (node (ref "DAC2") (pin "2") (pinfunction "VSS_2") (pintype "passive"))
      (node (ref "FLASH1") (pin "4") (pinfunction "GND_4") (pintype "unspecified"))
      (node (ref "FPC1") (pin "18") (pinfunction "18_18") (pintype "unspecified"))
      (node (ref "FPC1") (pin "2") (pinfunction "2_2") (pintype "unspecified"))
      (node (ref "FPC1") (pin "21") (pinfunction "21_21") (pintype "unspecified"))
      (node (ref "FPC1") (pin "24") (pinfunction "24_24") (pintype "unspecified"))
      (node (ref "FPC1") (pin "37") (pinfunction "37_37") (pintype "unspecified"))
      (node (ref "FPC1") (pin "4") (pinfunction "4_4") (pintype "unspecified"))
      (node (ref "FPC1") (pin "41") (pinfunction "41_41") (pintype "unspecified"))
      (node (ref "FPC1") (pin "50") (pinfunction "50_50") (pintype "unspecified"))
      (node (ref "FPC1") (pin "51") (pinfunction "51_51") (pintype "unspecified"))
      (node (ref "FPC1") (pin "52") (pinfunction "52_52") (pintype "unspecified"))
      (node (ref "FPC1") (pin "6") (pinfunction "6_6") (pintype "unspecified"))
      (node (ref "LED1") (pin "2") (pinfunction "2_2") (pintype "unspecified"))
      (node (ref "LED2") (pin "2") (pinfunction "2_2") (pintype "unspecified"))
      (node (ref "R14") (pin "1") (pinfunction "1_1") (pintype "unspecified"))
      (node (ref "R15") (pin "2") (pinfunction "2_2") (pintype "unspecified"))
      (node (ref "R20") (pin "1") (pinfunction "1_1") (pintype "unspecified"))
      (node (ref "RASPBERRY-BOTTOM2") (pin "1") (pinfunction "1_1") (pintype "unspecified"))
      (node (ref "RASPBERRY-BOTTOM2") (pin "12") (pinfunction "12_12") (pintype "unspecified"))
      (node (ref "RASPBERRY-BOTTOM2") (pin "15") (pinfunction "15_15") (pintype "unspecified"))
      (node (ref "RASPBERRY-BOTTOM2") (pin "22") (pinfunction "22_22") (pintype "unspecified"))
      (node (ref "RASPBERRY-BOTTOM2") (pin "28") (pinfunction "28_28") (pintype "unspecified"))
      (node (ref "RASPBERRY-BOTTOM2") (pin "31") (pinfunction "31_31") (pintype "unspecified"))
      (node (ref "RASPBERRY-BOTTOM2") (pin "36") (pinfunction "36_36") (pintype "unspecified"))
      (node (ref "RASPBERRY-BOTTOM2") (pin "8") (pinfunction "8_8") (pintype "unspecified"))
      (node (ref "RASPBERRY-TOP1") (pin "14") (pinfunction "14_14") (pintype "unspecified"))
      (node (ref "RASPBERRY-TOP1") (pin "20") (pinfunction "20_20") (pintype "unspecified"))
      (node (ref "RASPBERRY-TOP1") (pin "25") (pinfunction "25_25") (pintype "unspecified"))
      (node (ref "RASPBERRY-TOP1") (pin "30") (pinfunction "30_30") (pintype "unspecified"))
      (node (ref "RASPBERRY-TOP1") (pin "34") (pinfunction "34_34") (pintype "unspecified"))
      (node (ref "RASPBERRY-TOP1") (pin "39") (pinfunction "39_39") (pintype "unspecified"))
      (node (ref "RASPBERRY-TOP1") (pin "6") (pinfunction "6_6") (pintype "unspecified"))
      (node (ref "RASPBERRY-TOP1") (pin "9") (pinfunction "9_9") (pintype "unspecified"))
      (node (ref "SW1") (pin "1") (pinfunction "1_1") (pintype "unspecified"))
      (node (ref "U10") (pin "49") (pinfunction "EP_49") (pintype "unspecified"))
      (node (ref "U2") (pin "1") (pinfunction "ADJ(GND)_1") (pintype "unspecified"))
      (node (ref "U3") (pin "1") (pinfunction "ADJ(GND)_1") (pintype "unspecified"))
      (node (ref "VLOGIC1") (pin "11") (pinfunction "GND_11") (pintype "unspecified"))
    )
    (net (code "38") (name "GPIO0") (class "Default")
      (node (ref "RASPBERRY-BOTTOM2") (pin "13") (pinfunction "13_13") (pintype "unspecified"))
      (node (ref "RASPBERRY-TOP1") (pin "27") (pinfunction "27_27") (pintype "unspecified"))
    )
    (net (code "39") (name "GPIO1") (class "Default")
      (node (ref "RASPBERRY-BOTTOM2") (pin "14") (pinfunction "14_14") (pintype "unspecified"))
      (node (ref "RASPBERRY-TOP1") (pin "28") (pinfunction "28_28") (pintype "unspecified"))
    )
    (net (code "40") (name "GPIO4") (class "Default")
      (node (ref "RASPBERRY-BOTTOM2") (pin "33") (pinfunction "33_33") (pintype "unspecified"))
      (node (ref "RASPBERRY-TOP1") (pin "7") (pinfunction "7_7") (pintype "unspecified"))
    )
    (net (code "41") (name "GPIO5") (class "Default")
      (node (ref "RASPBERRY-BOTTOM2") (pin "11") (pinfunction "11_11") (pintype "unspecified"))
      (node (ref "RASPBERRY-TOP1") (pin "29") (pinfunction "29_29") (pintype "unspecified"))
    )
    (net (code "42") (name "GPIO6") (class "Default")
      (node (ref "RASPBERRY-BOTTOM2") (pin "9") (pinfunction "9_9") (pintype "unspecified"))
      (node (ref "RASPBERRY-TOP1") (pin "31") (pinfunction "31_31") (pintype "unspecified"))
    )
    (net (code "43") (name "GPIO7") (class "Default")
      (node (ref "RASPBERRY-BOTTOM2") (pin "16") (pinfunction "16_16") (pintype "unspecified"))
      (node (ref "RASPBERRY-TOP1") (pin "26") (pinfunction "26_26") (pintype "unspecified"))
    )
    (net (code "44") (name "GPIO8") (class "Default")
      (node (ref "RASPBERRY-BOTTOM2") (pin "18") (pinfunction "18_18") (pintype "unspecified"))
      (node (ref "RASPBERRY-TOP1") (pin "24") (pinfunction "24_24") (pintype "unspecified"))
    )
    (net (code "45") (name "GPIO9") (class "Default")
      (node (ref "RASPBERRY-BOTTOM2") (pin "19") (pinfunction "19_19") (pintype "unspecified"))
      (node (ref "RASPBERRY-TOP1") (pin "21") (pinfunction "21_21") (pintype "unspecified"))
    )
    (net (code "46") (name "GPIO10") (class "Default")
      (node (ref "RASPBERRY-BOTTOM2") (pin "21") (pinfunction "21_21") (pintype "unspecified"))
      (node (ref "RASPBERRY-TOP1") (pin "19") (pinfunction "19_19") (pintype "unspecified"))
    )
    (net (code "47") (name "GPIO11") (class "Default")
      (node (ref "RASPBERRY-BOTTOM2") (pin "17") (pinfunction "17_17") (pintype "unspecified"))
      (node (ref "RASPBERRY-TOP1") (pin "23") (pinfunction "23_23") (pintype "unspecified"))
    )
    (net (code "48") (name "GPIO12") (class "Default")
      (node (ref "RASPBERRY-BOTTOM2") (pin "10") (pinfunction "10_10") (pintype "unspecified"))
      (node (ref "RASPBERRY-TOP1") (pin "32") (pinfunction "32_32") (pintype "unspecified"))
    )
    (net (code "49") (name "GPIO13") (class "Default")
      (node (ref "RASPBERRY-BOTTOM2") (pin "7") (pinfunction "7_7") (pintype "unspecified"))
      (node (ref "RASPBERRY-TOP1") (pin "33") (pinfunction "33_33") (pintype "unspecified"))
    )
    (net (code "50") (name "GPIO17") (class "Default")
      (node (ref "RASPBERRY-BOTTOM2") (pin "29") (pinfunction "29_29") (pintype "unspecified"))
      (node (ref "RASPBERRY-TOP1") (pin "11") (pinfunction "11_11") (pintype "unspecified"))
    )
    (net (code "51") (name "GPIO18") (class "Default")
      (node (ref "RASPBERRY-BOTTOM2") (pin "30") (pinfunction "30_30") (pintype "unspecified"))
      (node (ref "RASPBERRY-TOP1") (pin "12") (pinfunction "12_12") (pintype "unspecified"))
    )
    (net (code "52") (name "GPIO22") (class "Default")
      (node (ref "RASPBERRY-BOTTOM2") (pin "25") (pinfunction "25_25") (pintype "unspecified"))
      (node (ref "RASPBERRY-TOP1") (pin "15") (pinfunction "15_15") (pintype "unspecified"))
    )
    (net (code "53") (name "GPIO23") (class "Default")
      (node (ref "RASPBERRY-BOTTOM2") (pin "26") (pinfunction "26_26") (pintype "unspecified"))
      (node (ref "RASPBERRY-TOP1") (pin "16") (pinfunction "16_16") (pintype "unspecified"))
    )
    (net (code "54") (name "GPIO24") (class "Default")
      (node (ref "RASPBERRY-BOTTOM2") (pin "24") (pinfunction "24_24") (pintype "unspecified"))
      (node (ref "RASPBERRY-TOP1") (pin "18") (pinfunction "18_18") (pintype "unspecified"))
    )
    (net (code "55") (name "GPIO25") (class "Default")
      (node (ref "RASPBERRY-BOTTOM2") (pin "20") (pinfunction "20_20") (pintype "unspecified"))
      (node (ref "RASPBERRY-TOP1") (pin "22") (pinfunction "22_22") (pintype "unspecified"))
    )
    (net (code "56") (name "GPIO27") (class "Default")
      (node (ref "RASPBERRY-BOTTOM2") (pin "27") (pinfunction "27_27") (pintype "unspecified"))
      (node (ref "RASPBERRY-TOP1") (pin "13") (pinfunction "13_13") (pintype "unspecified"))
    )
    (net (code "57") (name "I2C_SCL") (class "Default")
      (node (ref "DAC1") (pin "5") (pinfunction "SCL_5") (pintype "unspecified"))
      (node (ref "DAC2") (pin "5") (pinfunction "SCL_5") (pintype "unspecified"))
      (node (ref "FPC1") (pin "19") (pinfunction "19_19") (pintype "unspecified"))
      (node (ref "R16") (pin "1") (pinfunction "1_1") (pintype "unspecified"))
      (node (ref "RASPBERRY-BOTTOM2") (pin "35") (pinfunction "35_35") (pintype "unspecified"))
      (node (ref "RASPBERRY-TOP1") (pin "5") (pinfunction "5_5") (pintype "unspecified"))
      (node (ref "U10") (pin "37") (pinfunction "IOT_45a_G1_37") (pintype "unspecified"))
    )
    (net (code "58") (name "I2C_SDA") (class "Default")
      (node (ref "DAC1") (pin "4") (pinfunction "SDA_4") (pintype "bidirectional"))
      (node (ref "DAC2") (pin "4") (pinfunction "SDA_4") (pintype "bidirectional"))
      (node (ref "FPC1") (pin "20") (pinfunction "20_20") (pintype "unspecified"))
      (node (ref "R17") (pin "1") (pinfunction "1_1") (pintype "unspecified"))
      (node (ref "RASPBERRY-BOTTOM2") (pin "37") (pinfunction "37_37") (pintype "unspecified"))
      (node (ref "RASPBERRY-TOP1") (pin "3") (pinfunction "3_3") (pintype "unspecified"))
      (node (ref "U10") (pin "38") (pinfunction "IOT_50b_38") (pintype "unspecified"))
    )
    (net (code "59") (name "Net-(CLK1-VDD)") (class "Default")
      (node (ref "CLK1") (pin "4") (pinfunction "VDD_4") (pintype "unspecified"))
      (node (ref "RN2") (pin "6") (pinfunction "6_6") (pintype "unspecified"))
      (node (ref "RN2") (pin "7") (pinfunction "7_7") (pintype "unspecified"))
      (node (ref "RN2") (pin "8") (pinfunction "8_8") (pintype "unspecified"))
    )
    (net (code "60") (name "Net-(D1-A)") (class "Default")
      (node (ref "C1") (pin "1") (pinfunction "1_1") (pintype "input"))
      (node (ref "D1") (pin "2") (pinfunction "A_2") (pintype "unspecified"))
      (node (ref "U1") (pin "1") (pinfunction "1_1") (pintype "unspecified"))
    )
    (net (code "61") (name "Net-(DAC1-A0)") (class "Default")
      (node (ref "DAC1") (pin "6") (pinfunction "A0_6") (pintype "unspecified"))
      (node (ref "R20") (pin "2") (pinfunction "2_2") (pintype "unspecified"))
    )
    (net (code "62") (name "Net-(DAC2-A0)") (class "Default")
      (node (ref "DAC2") (pin "6") (pinfunction "A0_6") (pintype "unspecified"))
      (node (ref "R21") (pin "2") (pinfunction "2_2") (pintype "unspecified"))
    )
    (net (code "63") (name "Net-(FLASH1-CS#)") (class "Default")
      (node (ref "FLASH1") (pin "1") (pinfunction "CS#_1") (pintype "unspecified"))
      (node (ref "R10") (pin "1") (pinfunction "1_1") (pintype "unspecified"))
      (node (ref "R9") (pin "2") (pinfunction "2_2") (pintype "unspecified"))
    )
    (net (code "64") (name "Net-(FLASH1-HOLD#orRESET#(IO3))") (class "Default")
      (node (ref "FLASH1") (pin "7") (pinfunction "HOLD#orRESET#(IO3)_7") (pintype "unspecified"))
      (node (ref "R7") (pin "1") (pinfunction "1_1") (pintype "unspecified"))
    )
    (net (code "65") (name "Net-(FLASH1-WP#(IO2))") (class "Default")
      (node (ref "FLASH1") (pin "3") (pinfunction "WP#(IO2)_3") (pintype "unspecified"))
      (node (ref "R11") (pin "1") (pinfunction "1_1") (pintype "unspecified"))
    )
    (net (code "66") (name "Net-(FPC1-Pad25)") (class "Default")
      (node (ref "FPC1") (pin "25") (pinfunction "25_25") (pintype "unspecified"))
      (node (ref "RN4") (pin "1") (pinfunction "1_1") (pintype "unspecified"))
    )
    (net (code "67") (name "Net-(FPC1-Pad26)") (class "Default")
      (node (ref "FPC1") (pin "26") (pinfunction "26_26") (pintype "unspecified"))
      (node (ref "RN4") (pin "2") (pinfunction "2_2") (pintype "unspecified"))
    )
    (net (code "68") (name "Net-(FPC1-Pad27)") (class "Default")
      (node (ref "FPC1") (pin "27") (pinfunction "27_27") (pintype "unspecified"))
      (node (ref "RN4") (pin "3") (pinfunction "3_3") (pintype "unspecified"))
    )
    (net (code "69") (name "Net-(FPC1-Pad28)") (class "Default")
      (node (ref "FPC1") (pin "28") (pinfunction "28_28") (pintype "unspecified"))
      (node (ref "RN4") (pin "4") (pinfunction "4_4") (pintype "unspecified"))
    )
    (net (code "70") (name "Net-(FPC1-Pad29)") (class "Default")
      (node (ref "FPC1") (pin "29") (pinfunction "29_29") (pintype "unspecified"))
      (node (ref "RN5") (pin "1") (pinfunction "1_1") (pintype "unspecified"))
    )
    (net (code "71") (name "Net-(FPC1-Pad30)") (class "Default")
      (node (ref "FPC1") (pin "30") (pinfunction "30_30") (pintype "unspecified"))
      (node (ref "RN5") (pin "2") (pinfunction "2_2") (pintype "unspecified"))
    )
    (net (code "72") (name "Net-(FPC1-Pad31)") (class "Default")
      (node (ref "FPC1") (pin "31") (pinfunction "31_31") (pintype "unspecified"))
      (node (ref "RN5") (pin "3") (pinfunction "3_3") (pintype "unspecified"))
    )
    (net (code "73") (name "Net-(FPC1-Pad32)") (class "Default")
      (node (ref "FPC1") (pin "32") (pinfunction "32_32") (pintype "unspecified"))
      (node (ref "RN5") (pin "4") (pinfunction "4_4") (pintype "unspecified"))
    )
    (net (code "74") (name "Net-(FPC1-Pad33)") (class "Default")
      (node (ref "FPC1") (pin "33") (pinfunction "33_33") (pintype "unspecified"))
      (node (ref "RN6") (pin "1") (pinfunction "1_1") (pintype "unspecified"))
    )
    (net (code "75") (name "Net-(FPC1-Pad34)") (class "Default")
      (node (ref "FPC1") (pin "34") (pinfunction "34_34") (pintype "unspecified"))
      (node (ref "RN6") (pin "2") (pinfunction "2_2") (pintype "unspecified"))
    )
    (net (code "76") (name "Net-(FPC1-Pad35)") (class "Default")
      (node (ref "FPC1") (pin "35") (pinfunction "35_35") (pintype "unspecified"))
      (node (ref "RN6") (pin "3") (pinfunction "3_3") (pintype "unspecified"))
    )
    (net (code "77") (name "Net-(FPC1-Pad36)") (class "Default")
      (node (ref "FPC1") (pin "36") (pinfunction "36_36") (pintype "unspecified"))
      (node (ref "RN6") (pin "4") (pinfunction "4_4") (pintype "unspecified"))
    )
    (net (code "78") (name "Net-(FPC1-Pad42)") (class "Default")
      (node (ref "FPC1") (pin "42") (pinfunction "42_42") (pintype "unspecified"))
      (node (ref "RN1") (pin "1") (pinfunction "1_1") (pintype "unspecified"))
    )
    (net (code "79") (name "Net-(FPC1-Pad43)") (class "Default")
      (node (ref "FPC1") (pin "43") (pinfunction "43_43") (pintype "unspecified"))
      (node (ref "RN1") (pin "2") (pinfunction "2_2") (pintype "unspecified"))
    )
    (net (code "80") (name "Net-(FPC1-Pad44)") (class "Default")
      (node (ref "FPC1") (pin "44") (pinfunction "44_44") (pintype "unspecified"))
      (node (ref "RN1") (pin "3") (pinfunction "3_3") (pintype "unspecified"))
    )
    (net (code "81") (name "Net-(FPC1-Pad45)") (class "Default")
      (node (ref "FPC1") (pin "45") (pinfunction "45_45") (pintype "unspecified"))
      (node (ref "RN1") (pin "4") (pinfunction "4_4") (pintype "unspecified"))
    )
    (net (code "82") (name "Net-(FPC1-Pad46)") (class "Default")
      (node (ref "FPC1") (pin "46") (pinfunction "46_46") (pintype "unspecified"))
      (node (ref "RN3") (pin "1") (pinfunction "1_1") (pintype "unspecified"))
    )
    (net (code "83") (name "Net-(FPC1-Pad47)") (class "Default")
      (node (ref "FPC1") (pin "47") (pinfunction "47_47") (pintype "unspecified"))
      (node (ref "RN3") (pin "2") (pinfunction "2_2") (pintype "unspecified"))
    )
    (net (code "84") (name "Net-(FPC1-Pad48)") (class "Default")
      (node (ref "FPC1") (pin "48") (pinfunction "48_48") (pintype "unspecified"))
      (node (ref "RN3") (pin "3") (pinfunction "3_3") (pintype "unspecified"))
    )
    (net (code "85") (name "Net-(FPC1-Pad49)") (class "Default")
      (node (ref "FPC1") (pin "49") (pinfunction "49_49") (pintype "unspecified"))
      (node (ref "RN3") (pin "4") (pinfunction "4_4") (pintype "unspecified"))
    )
    (net (code "86") (name "Net-(LED2-Pad1)") (class "Default")
      (node (ref "LED2") (pin "1") (pinfunction "1_1") (pintype "unspecified"))
      (node (ref "R5") (pin "1") (pinfunction "1_1") (pintype "input"))
    )
    (net (code "87") (name "Net-(RN2-Pad1)") (class "Default")
      (node (ref "RN2") (pin "1") (pinfunction "1_1") (pintype "unspecified"))
      (node (ref "RN2") (pin "2") (pinfunction "2_2") (pintype "unspecified"))
      (node (ref "RN2") (pin "3") (pinfunction "3_3") (pintype "unspecified"))
      (node (ref "RN2") (pin "4") (pinfunction "4_4") (pintype "unspecified"))
    )
    (net (code "88") (name "PWM-RGB0") (class "Default")
      (node (ref "FPC1") (pin "38") (pinfunction "38_38") (pintype "unspecified"))
      (node (ref "U10") (pin "39") (pinfunction "RGB0_39") (pintype "unspecified"))
    )
    (net (code "89") (name "PWM-RGB1") (class "Default")
      (node (ref "FPC1") (pin "39") (pinfunction "39_39") (pintype "unspecified"))
      (node (ref "U10") (pin "40") (pinfunction "RGB1_40") (pintype "unspecified"))
    )
    (net (code "90") (name "PWM-RGB2") (class "Default")
      (node (ref "FPC1") (pin "40") (pinfunction "40_40") (pintype "unspecified"))
      (node (ref "U10") (pin "41") (pinfunction "RGB2_41") (pintype "unspecified"))
    )
    (net (code "91") (name "PWR1v2") (class "Default")
      (node (ref "C8") (pin "1") (pinfunction "1_1") (pintype "input"))
      (node (ref "C9") (pin "2") (pinfunction "2_2") (pintype "input"))
      (node (ref "R1") (pin "1") (pinfunction "1_1") (pintype "unspecified"))
      (node (ref "R2") (pin "1") (pinfunction "1_1") (pintype "unspecified"))
      (node (ref "U3") (pin "4") (pinfunction "TAB_4") (pintype "unspecified"))
    )
    (net (code "92") (name "PWR3v3") (class "Default")
      (node (ref "C6") (pin "1") (pinfunction "1_1") (pintype "input"))
      (node (ref "C7") (pin "2") (pinfunction "2_2") (pintype "input"))
      (node (ref "D2") (pin "2") (pinfunction "A_2") (pintype "unspecified"))
      (node (ref "R3") (pin "1") (pinfunction "1_1") (pintype "unspecified"))
      (node (ref "U2") (pin "4") (pinfunction "TAB_4") (pintype "unspecified"))
    )
    (net (code "93") (name "PWR5v") (class "Default")
      (node (ref "C2") (pin "1") (pinfunction "1_1") (pintype "input"))
      (node (ref "C3") (pin "2") (pinfunction "2_2") (pintype "input"))
      (node (ref "C4") (pin "2") (pinfunction "2_2") (pintype "input"))
      (node (ref "C5") (pin "2") (pinfunction "2_2") (pintype "input"))
      (node (ref "D1") (pin "1") (pinfunction "C_1") (pintype "unspecified"))
      (node (ref "R5") (pin "2") (pinfunction "2_2") (pintype "input"))
      (node (ref "U2") (pin "3") (pinfunction "VIN_3") (pintype "unspecified"))
      (node (ref "U3") (pin "3") (pinfunction "VIN_3") (pintype "unspecified"))
      (node (ref "VLOGIC1") (pin "19") (pinfunction "VCCB_19") (pintype "unspecified"))
    )
    (net (code "94") (name "SCLK-ICE") (class "Default")
      (node (ref "FLASH1") (pin "6") (pinfunction "CLK_6") (pintype "unspecified"))
      (node (ref "R8") (pin "1") (pinfunction "1_1") (pintype "unspecified"))
      (node (ref "RASPBERRY-BOTTOM2") (pin "6") (pinfunction "6_6") (pintype "unspecified"))
      (node (ref "RASPBERRY-TOP1") (pin "36") (pinfunction "36_36") (pintype "unspecified"))
      (node (ref "U10") (pin "15") (pinfunction "IOB_34a_SPI_SCK_15") (pintype "unspecified"))
    )
    (net (code "95") (name "SDI") (class "Default")
      (node (ref "FLASH1") (pin "5") (pinfunction "DI(IO0)_5") (pintype "unspecified"))
      (node (ref "R13") (pin "1") (pinfunction "1_1") (pintype "unspecified"))
      (node (ref "RASPBERRY-BOTTOM2") (pin "4") (pinfunction "4_4") (pintype "unspecified"))
      (node (ref "RASPBERRY-TOP1") (pin "38") (pinfunction "38_38") (pintype "unspecified"))
    )
    (net (code "96") (name "SDI-ICE") (class "Default")
      (node (ref "R12") (pin "2") (pinfunction "2_2") (pintype "unspecified"))
      (node (ref "U10") (pin "17") (pinfunction "IOB_33b_SPI_SI_17") (pintype "unspecified"))
    )
    (net (code "97") (name "SDO") (class "Default")
      (node (ref "FLASH1") (pin "2") (pinfunction "DO(IO1)_2") (pintype "unspecified"))
      (node (ref "R12") (pin "1") (pinfunction "1_1") (pintype "unspecified"))
      (node (ref "RASPBERRY-BOTTOM2") (pin "5") (pinfunction "5_5") (pintype "unspecified"))
      (node (ref "RASPBERRY-TOP1") (pin "35") (pinfunction "35_35") (pintype "unspecified"))
    )
    (net (code "98") (name "SDO-ICE") (class "Default")
      (node (ref "R13") (pin "2") (pinfunction "2_2") (pintype "unspecified"))
      (node (ref "U10") (pin "14") (pinfunction "IOB_32a_SPI_SO_14") (pintype "unspecified"))
    )
    (net (code "99") (name "SHDN") (class "Default")
      (node (ref "ADC1") (pin "10") (pinfunction "SHDN#_10") (pintype "unspecified"))
      (node (ref "R14") (pin "2") (pinfunction "2_2") (pintype "unspecified"))
      (node (ref "U10") (pin "43") (pinfunction "IOT_49a_43") (pintype "unspecified"))
    )
    (net (code "100") (name "UART-RXD") (class "Default")
      (node (ref "FPC1") (pin "22") (pinfunction "22_22") (pintype "unspecified"))
      (node (ref "R18") (pin "1") (pinfunction "1_1") (pintype "unspecified"))
      (node (ref "RASPBERRY-BOTTOM2") (pin "34") (pinfunction "34_34") (pintype "unspecified"))
      (node (ref "RASPBERRY-TOP1") (pin "8") (pinfunction "8_8") (pintype "unspecified"))
      (node (ref "U10") (pin "4") (pinfunction "IOB_8a_4") (pintype "unspecified"))
    )
    (net (code "101") (name "UART-TXD") (class "Default")
      (node (ref "FPC1") (pin "23") (pinfunction "23_23") (pintype "unspecified"))
      (node (ref "R19") (pin "1") (pinfunction "1_1") (pintype "unspecified"))
      (node (ref "RASPBERRY-BOTTOM2") (pin "32") (pinfunction "32_32") (pintype "unspecified"))
      (node (ref "RASPBERRY-TOP1") (pin "10") (pinfunction "10_10") (pintype "unspecified"))
      (node (ref "U10") (pin "6") (pinfunction "IOB_13b_6") (pintype "unspecified"))
    )
    (net (code "102") (name "Vcc") (class "Default")
      (node (ref "C16") (pin "2") (pinfunction "2_2") (pintype "input"))
      (node (ref "C17") (pin "2") (pinfunction "2_2") (pintype "input"))
      (node (ref "C18") (pin "2") (pinfunction "2_2") (pintype "input"))
      (node (ref "C19") (pin "2") (pinfunction "2_2") (pintype "input"))
      (node (ref "C20") (pin "2") (pinfunction "2_2") (pintype "input"))
      (node (ref "C21") (pin "1") (pinfunction "1_1") (pintype "input"))
      (node (ref "R2") (pin "2") (pinfunction "2_2") (pintype "unspecified"))
      (node (ref "U10") (pin "30") (pinfunction "VCC_30") (pintype "unspecified"))
      (node (ref "U10") (pin "5") (pinfunction "VCC_5") (pintype "unspecified"))
    )
    (net (code "103") (name "Vcc-5v") (class "Default")
      (node (ref "RASPBERRY-BOTTOM2") (pin "38") (pinfunction "38_38") (pintype "unspecified"))
      (node (ref "RASPBERRY-TOP1") (pin "4") (pinfunction "4_4") (pintype "unspecified"))
      (node (ref "U1") (pin "2") (pinfunction "2_2") (pintype "unspecified"))
    )
    (net (code "104") (name "Vccpll") (class "Default")
      (node (ref "C10") (pin "1") (pinfunction "1_1") (pintype "input"))
      (node (ref "C11") (pin "2") (pinfunction "2_2") (pintype "input"))
      (node (ref "C12") (pin "2") (pinfunction "2_2") (pintype "input"))
      (node (ref "C13") (pin "2") (pinfunction "2_2") (pintype "input"))
      (node (ref "C14") (pin "2") (pinfunction "2_2") (pintype "input"))
      (node (ref "C15") (pin "2") (pinfunction "2_2") (pintype "input"))
      (node (ref "R1") (pin "2") (pinfunction "2_2") (pintype "unspecified"))
      (node (ref "U10") (pin "29") (pinfunction "VCCPLL_29") (pintype "unspecified"))
    )
    (net (code "105") (name "Vlogic-00") (class "Default")
      (node (ref "RN3") (pin "5") (pinfunction "5_5") (pintype "unspecified"))
      (node (ref "VLOGIC1") (pin "20") (pinfunction "B1_20") (pintype "unspecified"))
    )
    (net (code "106") (name "Vlogic-00in{slash}out") (class "Default")
      (node (ref "U10") (pin "36") (pinfunction "IOT_48b_36") (pintype "unspecified"))
      (node (ref "VLOGIC1") (pin "1") (pinfunction "A1_1") (pintype "unspecified"))
    )
    (net (code "107") (name "Vlogic-01") (class "Default")
      (node (ref "RN3") (pin "6") (pinfunction "6_6") (pintype "unspecified"))
      (node (ref "VLOGIC1") (pin "18") (pinfunction "B2_18") (pintype "unspecified"))
    )
    (net (code "108") (name "Vlogic-01in{slash}out") (class "Default")
      (node (ref "U10") (pin "34") (pinfunction "IOT_44b_34") (pintype "unspecified"))
      (node (ref "VLOGIC1") (pin "3") (pinfunction "A2_3") (pintype "unspecified"))
    )
    (net (code "109") (name "Vlogic-02") (class "Default")
      (node (ref "RN3") (pin "7") (pinfunction "7_7") (pintype "unspecified"))
      (node (ref "VLOGIC1") (pin "17") (pinfunction "B3_17") (pintype "unspecified"))
    )
    (net (code "110") (name "Vlogic-02in{slash}out") (class "Default")
      (node (ref "U10") (pin "32") (pinfunction "IOT_43a_32") (pintype "unspecified"))
      (node (ref "VLOGIC1") (pin "4") (pinfunction "A3_4") (pintype "unspecified"))
    )
    (net (code "111") (name "Vlogic-03") (class "Default")
      (node (ref "RN3") (pin "8") (pinfunction "8_8") (pintype "unspecified"))
      (node (ref "VLOGIC1") (pin "16") (pinfunction "B4_16") (pintype "unspecified"))
    )
    (net (code "112") (name "Vlogic-03in{slash}out") (class "Default")
      (node (ref "U10") (pin "31") (pinfunction "IOT_42b_31") (pintype "unspecified"))
      (node (ref "VLOGIC1") (pin "5") (pinfunction "A4_5") (pintype "unspecified"))
    )
    (net (code "113") (name "Vlogic-04") (class "Default")
      (node (ref "RN1") (pin "5") (pinfunction "5_5") (pintype "unspecified"))
      (node (ref "VLOGIC1") (pin "15") (pinfunction "B5_15") (pintype "unspecified"))
    )
    (net (code "114") (name "Vlogic-04in{slash}out") (class "Default")
      (node (ref "U10") (pin "28") (pinfunction "IOT_41a_28") (pintype "unspecified"))
      (node (ref "VLOGIC1") (pin "6") (pinfunction "A5_6") (pintype "unspecified"))
    )
    (net (code "115") (name "Vlogic-05") (class "Default")
      (node (ref "RN1") (pin "6") (pinfunction "6_6") (pintype "unspecified"))
      (node (ref "VLOGIC1") (pin "14") (pinfunction "B6_14") (pintype "unspecified"))
    )
    (net (code "116") (name "Vlogic-05in{slash}out") (class "Default")
      (node (ref "U10") (pin "27") (pinfunction "IOT_38b_27") (pintype "unspecified"))
      (node (ref "VLOGIC1") (pin "7") (pinfunction "A6_7") (pintype "unspecified"))
    )
    (net (code "117") (name "Vlogic-06") (class "Default")
      (node (ref "RN1") (pin "7") (pinfunction "7_7") (pintype "unspecified"))
      (node (ref "VLOGIC1") (pin "13") (pinfunction "B7_13") (pintype "unspecified"))
    )
    (net (code "118") (name "Vlogic-06in{slash}out") (class "Default")
      (node (ref "U10") (pin "26") (pinfunction "IOT_39a_26") (pintype "unspecified"))
      (node (ref "VLOGIC1") (pin "8") (pinfunction "A7_8") (pintype "unspecified"))
    )
    (net (code "119") (name "Vlogic-07") (class "Default")
      (node (ref "RN1") (pin "8") (pinfunction "8_8") (pintype "unspecified"))
      (node (ref "VLOGIC1") (pin "12") (pinfunction "B8_12") (pintype "unspecified"))
    )
    (net (code "120") (name "Vlogic-07in{slash}out") (class "Default")
      (node (ref "U10") (pin "25") (pinfunction "IOT_36b_25") (pintype "unspecified"))
      (node (ref "VLOGIC1") (pin "9") (pinfunction "A8_9") (pintype "unspecified"))
    )
    (net (code "121") (name "Vlogic_OE") (class "Default")
      (node (ref "R15") (pin "1") (pinfunction "1_1") (pintype "unspecified"))
      (node (ref "U10") (pin "42") (pinfunction "IOT_51a_42") (pintype "unspecified"))
      (node (ref "VLOGIC1") (pin "10") (pinfunction "OE_10") (pintype "unspecified"))
    )
    (net (code "122") (name "Vpp_2v5") (class "Default")
      (node (ref "C22") (pin "1") (pinfunction "1_1") (pintype "input"))
      (node (ref "C23") (pin "2") (pinfunction "2_2") (pintype "input"))
      (node (ref "C24") (pin "2") (pinfunction "2_2") (pintype "input"))
      (node (ref "C25") (pin "2") (pinfunction "2_2") (pintype "input"))
      (node (ref "C26") (pin "2") (pinfunction "2_2") (pintype "input"))
      (node (ref "C27") (pin "2") (pinfunction "2_2") (pintype "input"))
      (node (ref "D2") (pin "1") (pinfunction "C_1") (pintype "unspecified"))
      (node (ref "U10") (pin "24") (pinfunction "VPP_2V5_24") (pintype "unspecified"))
    )
    (net (code "123") (name "unconnected-(U2-VOUT(TAB)-Pad2)") (class "Default")
      (node (ref "U2") (pin "2") (pinfunction "VOUT(TAB)_2") (pintype "unspecified+no_connect"))
    )
    (net (code "124") (name "unconnected-(U3-VOUT(TAB)-Pad2)") (class "Default")
      (node (ref "U3") (pin "2") (pinfunction "VOUT(TAB)_2") (pintype "unspecified+no_connect"))
    )
  )
)
